# PX4uNode_V0_2_1.net
KiCad netlist of a schematic drawn in EAGLE
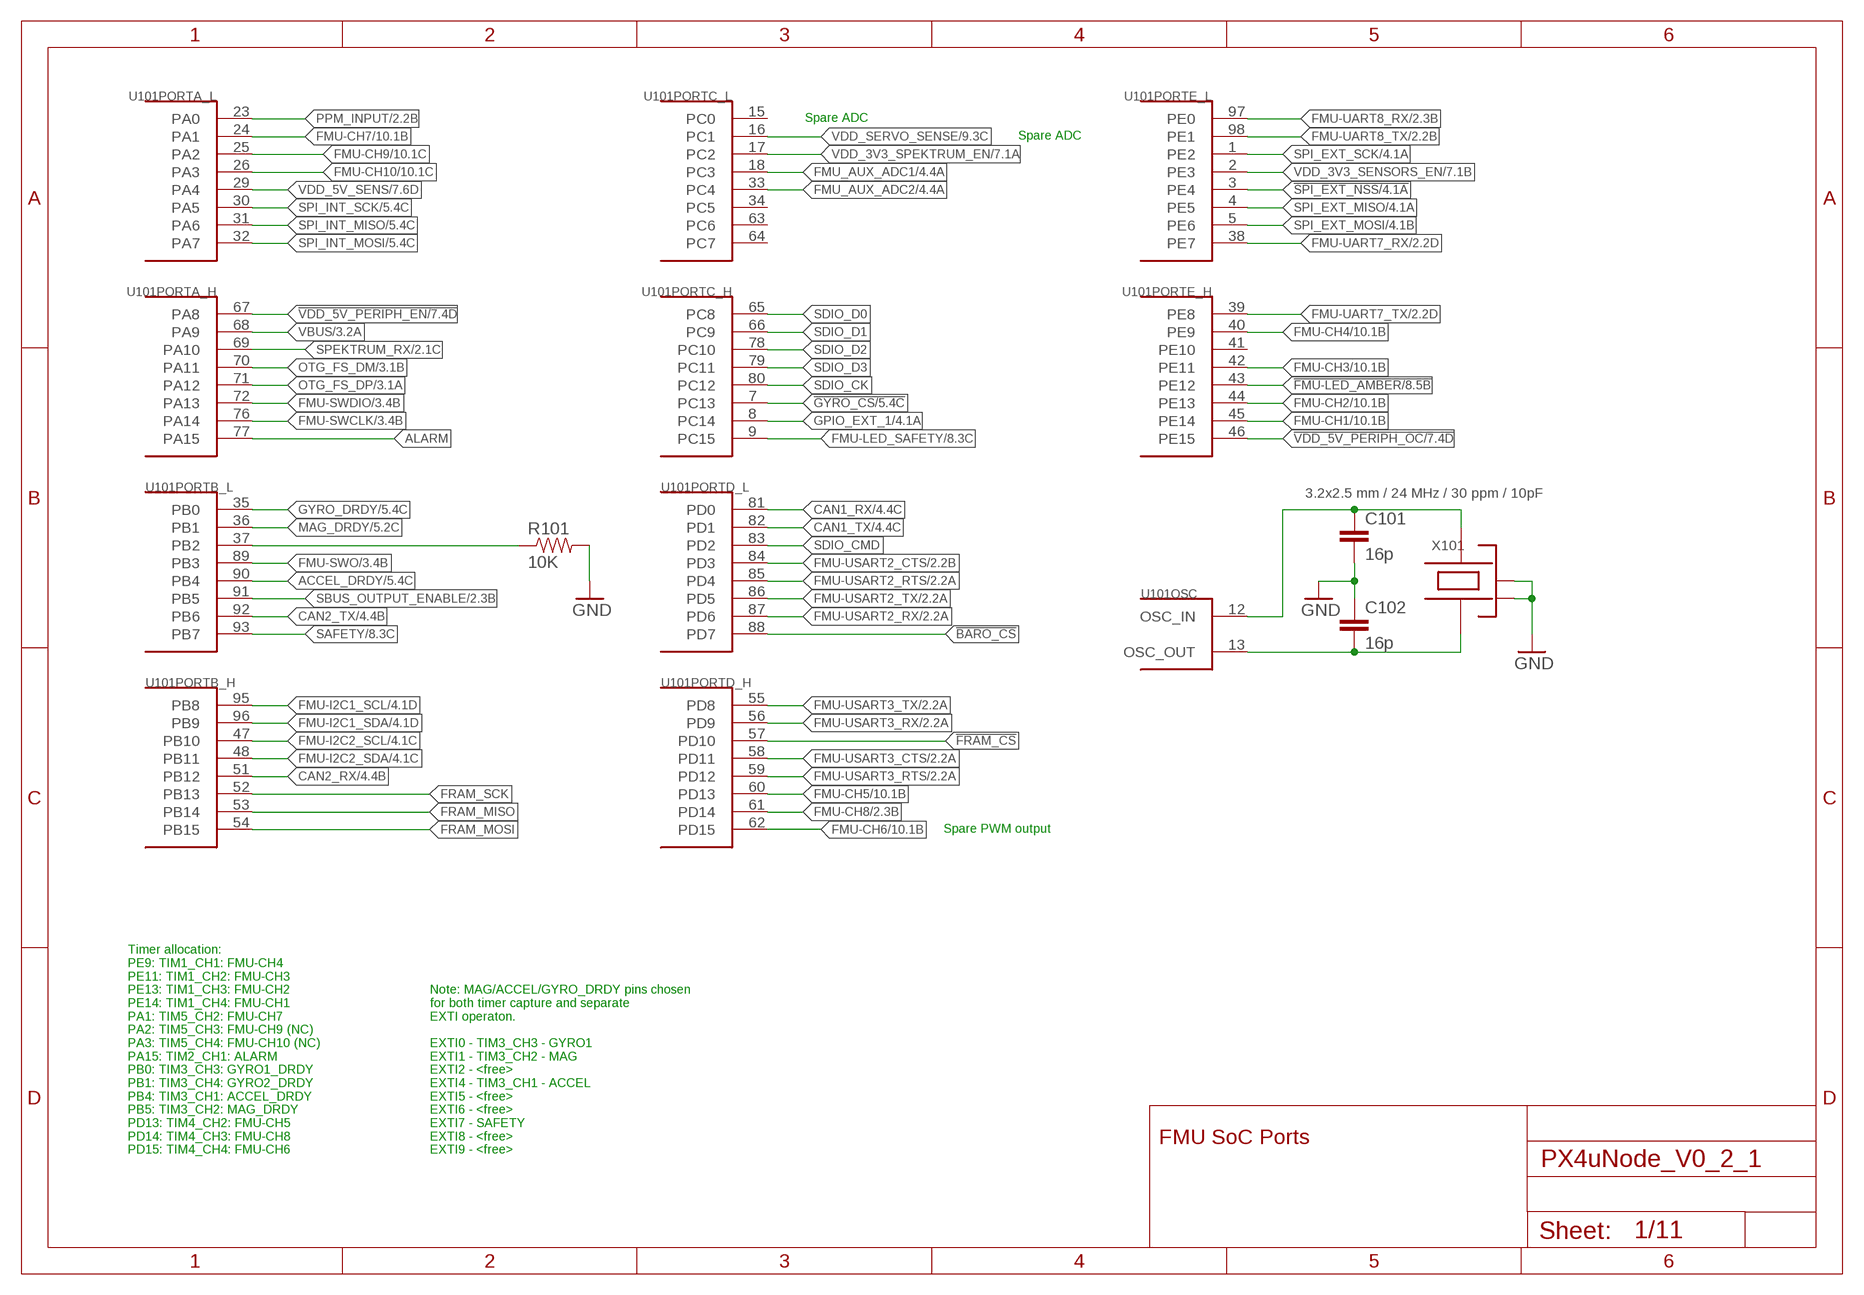
[diagram p0: schematic, sheet 1]
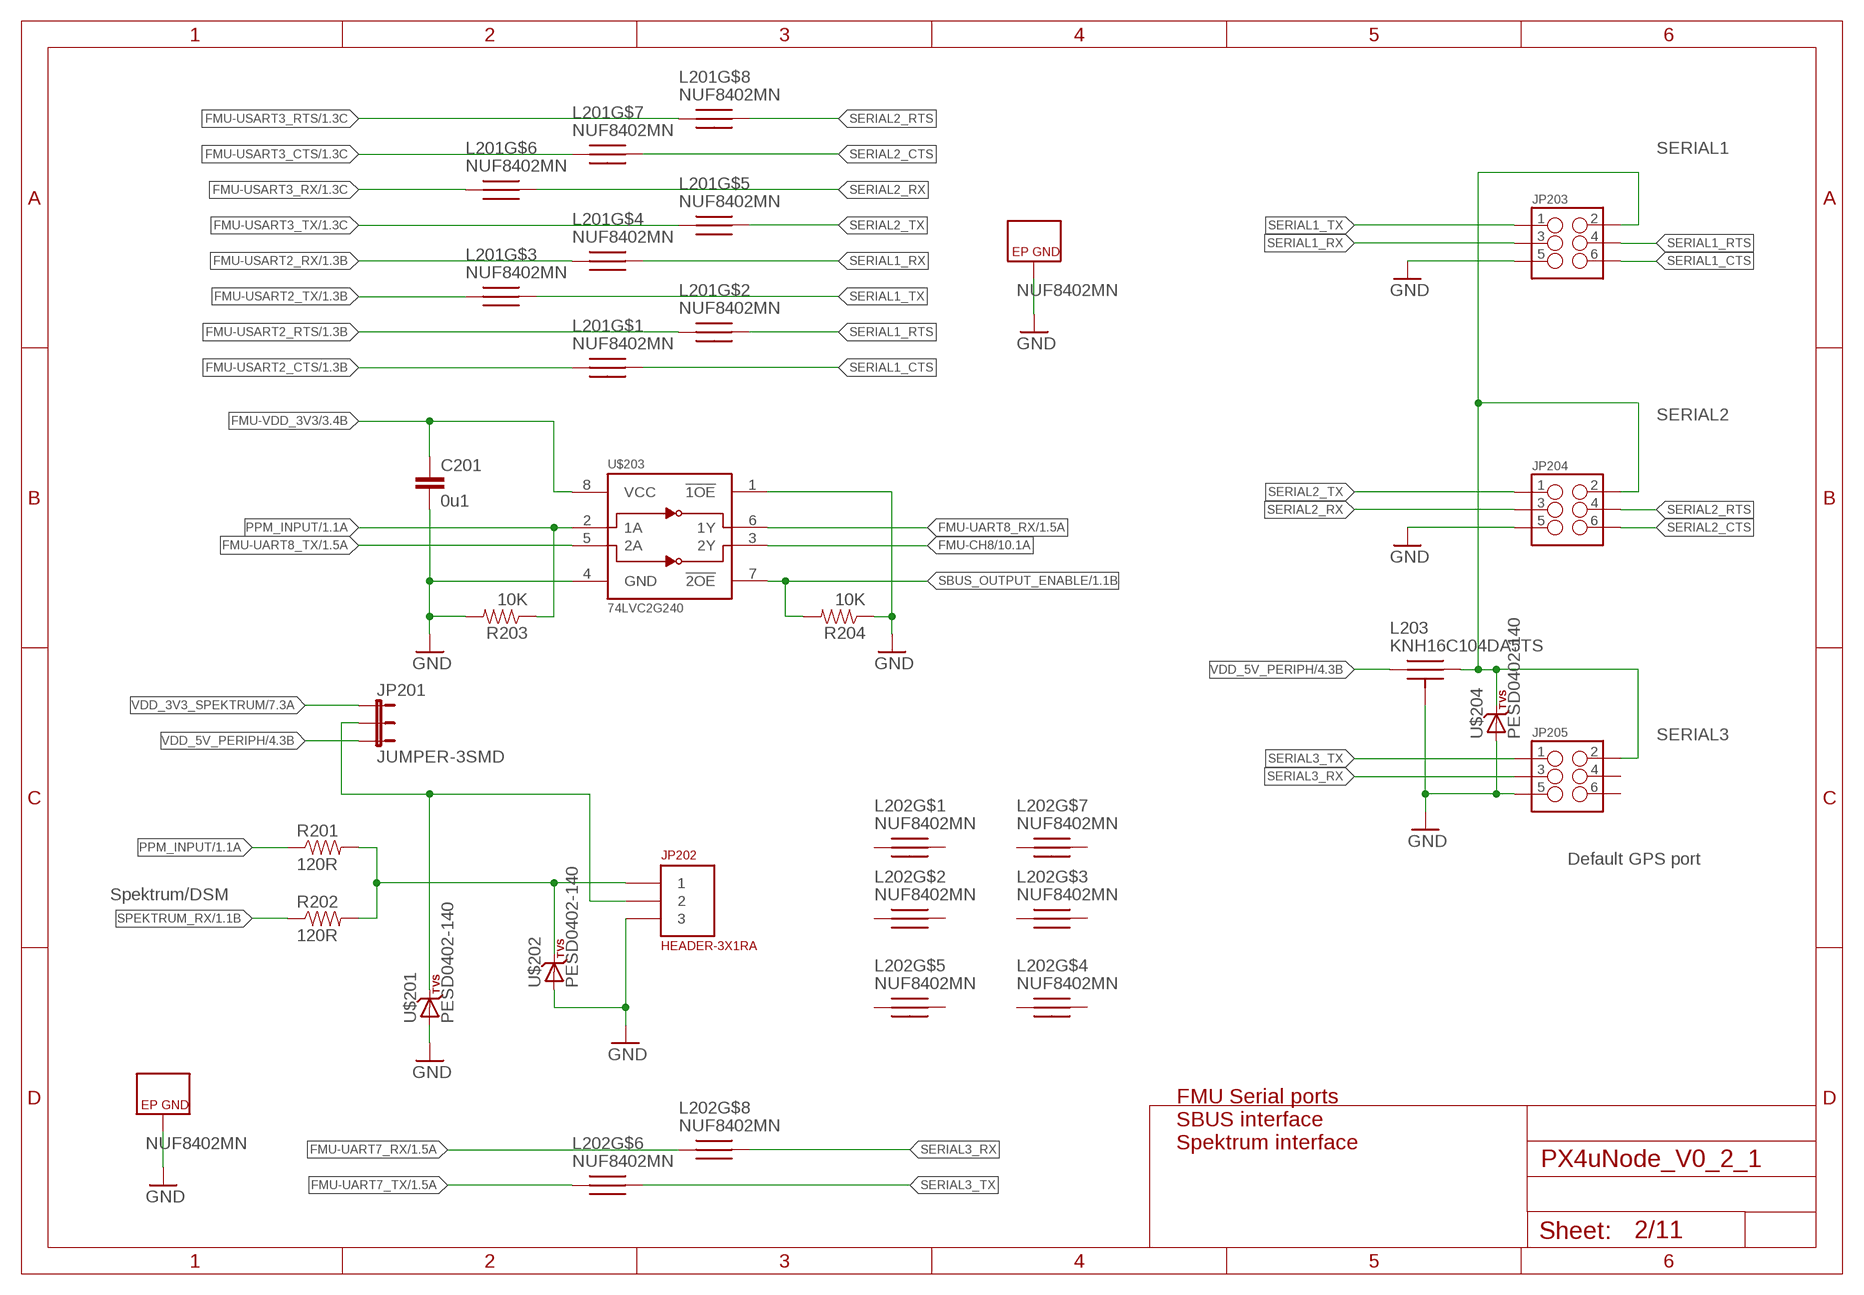
[diagram p1: schematic, sheet 2]
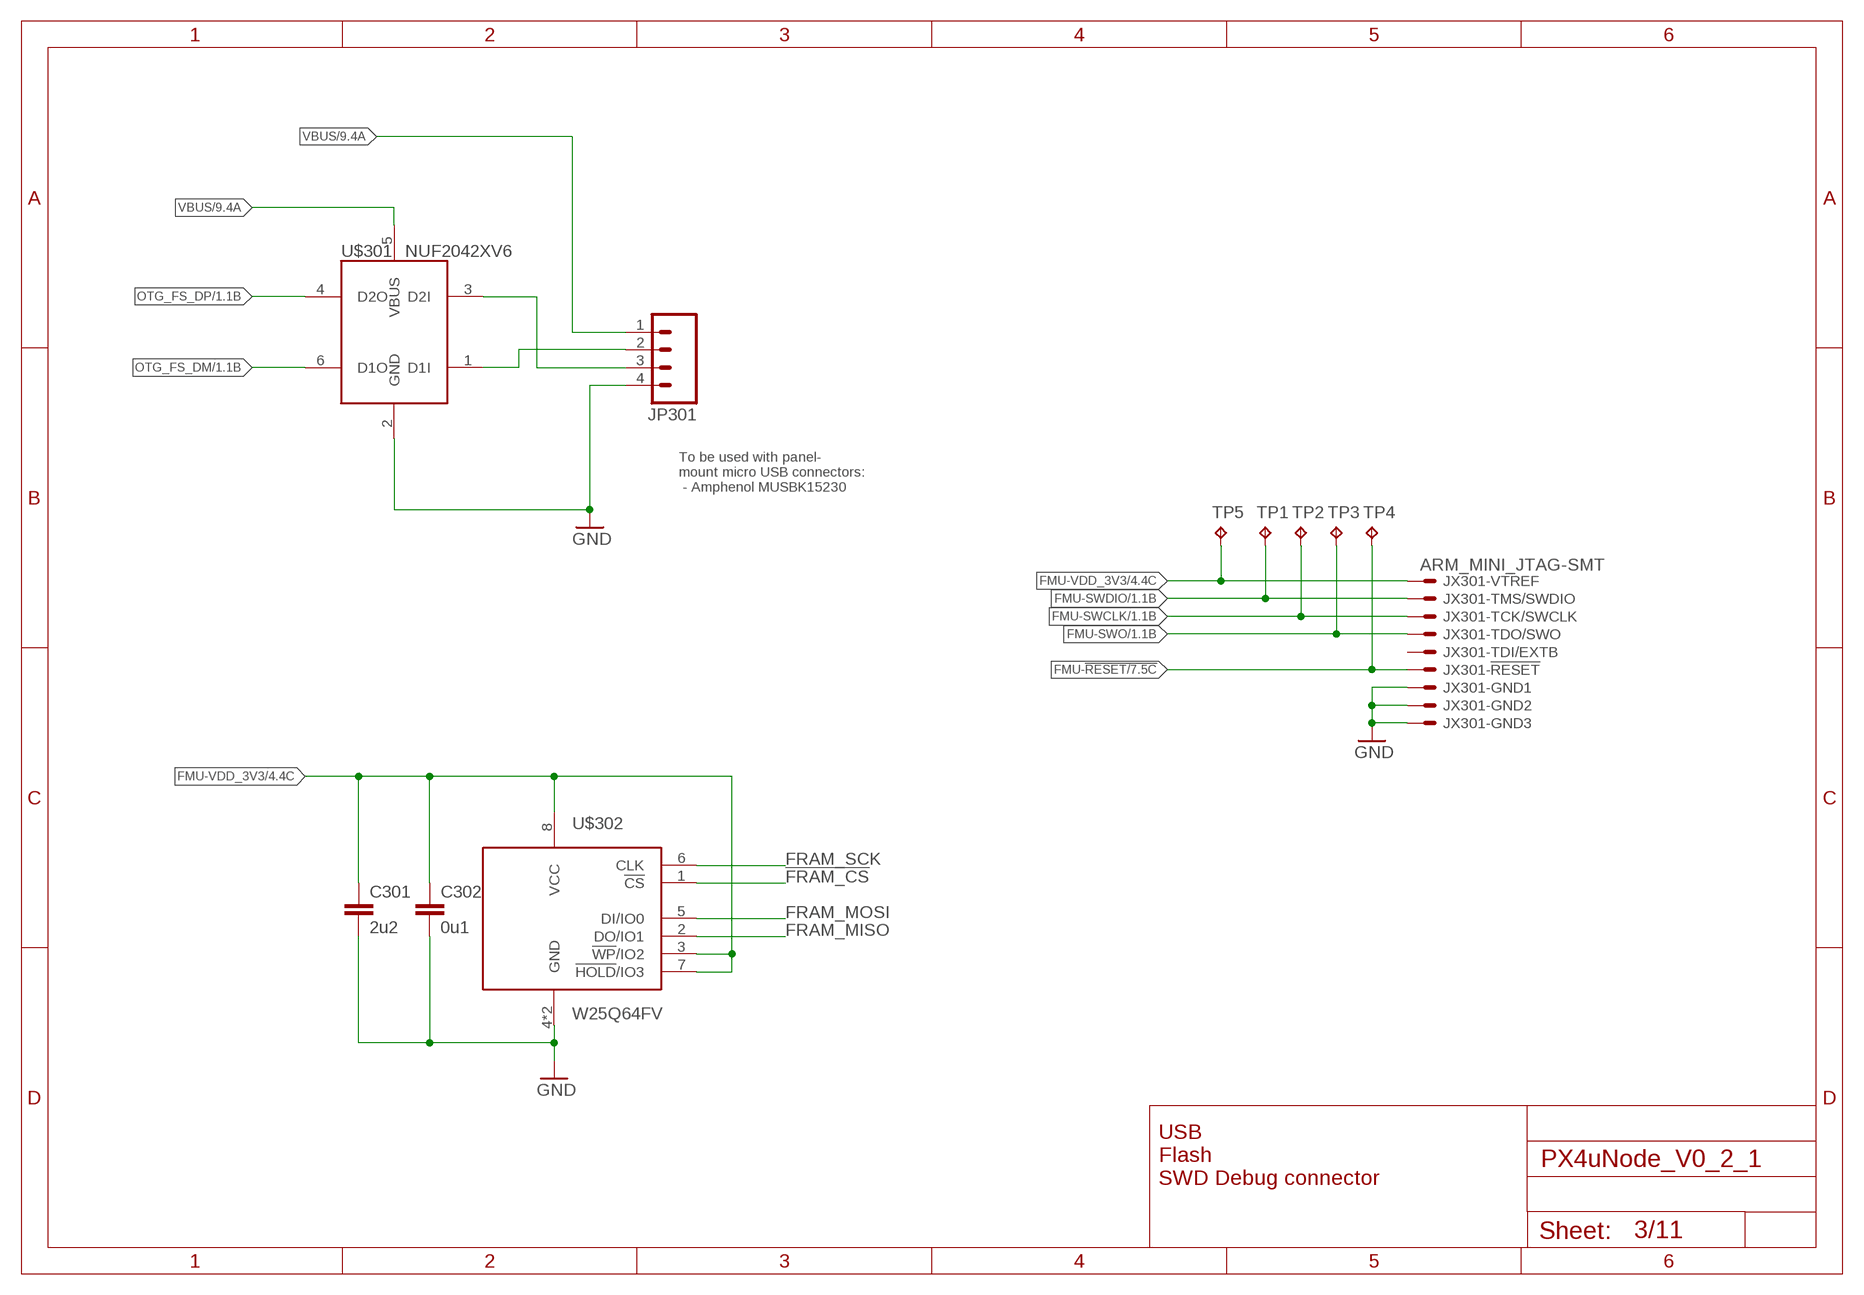
[diagram p2: schematic, sheet 3]
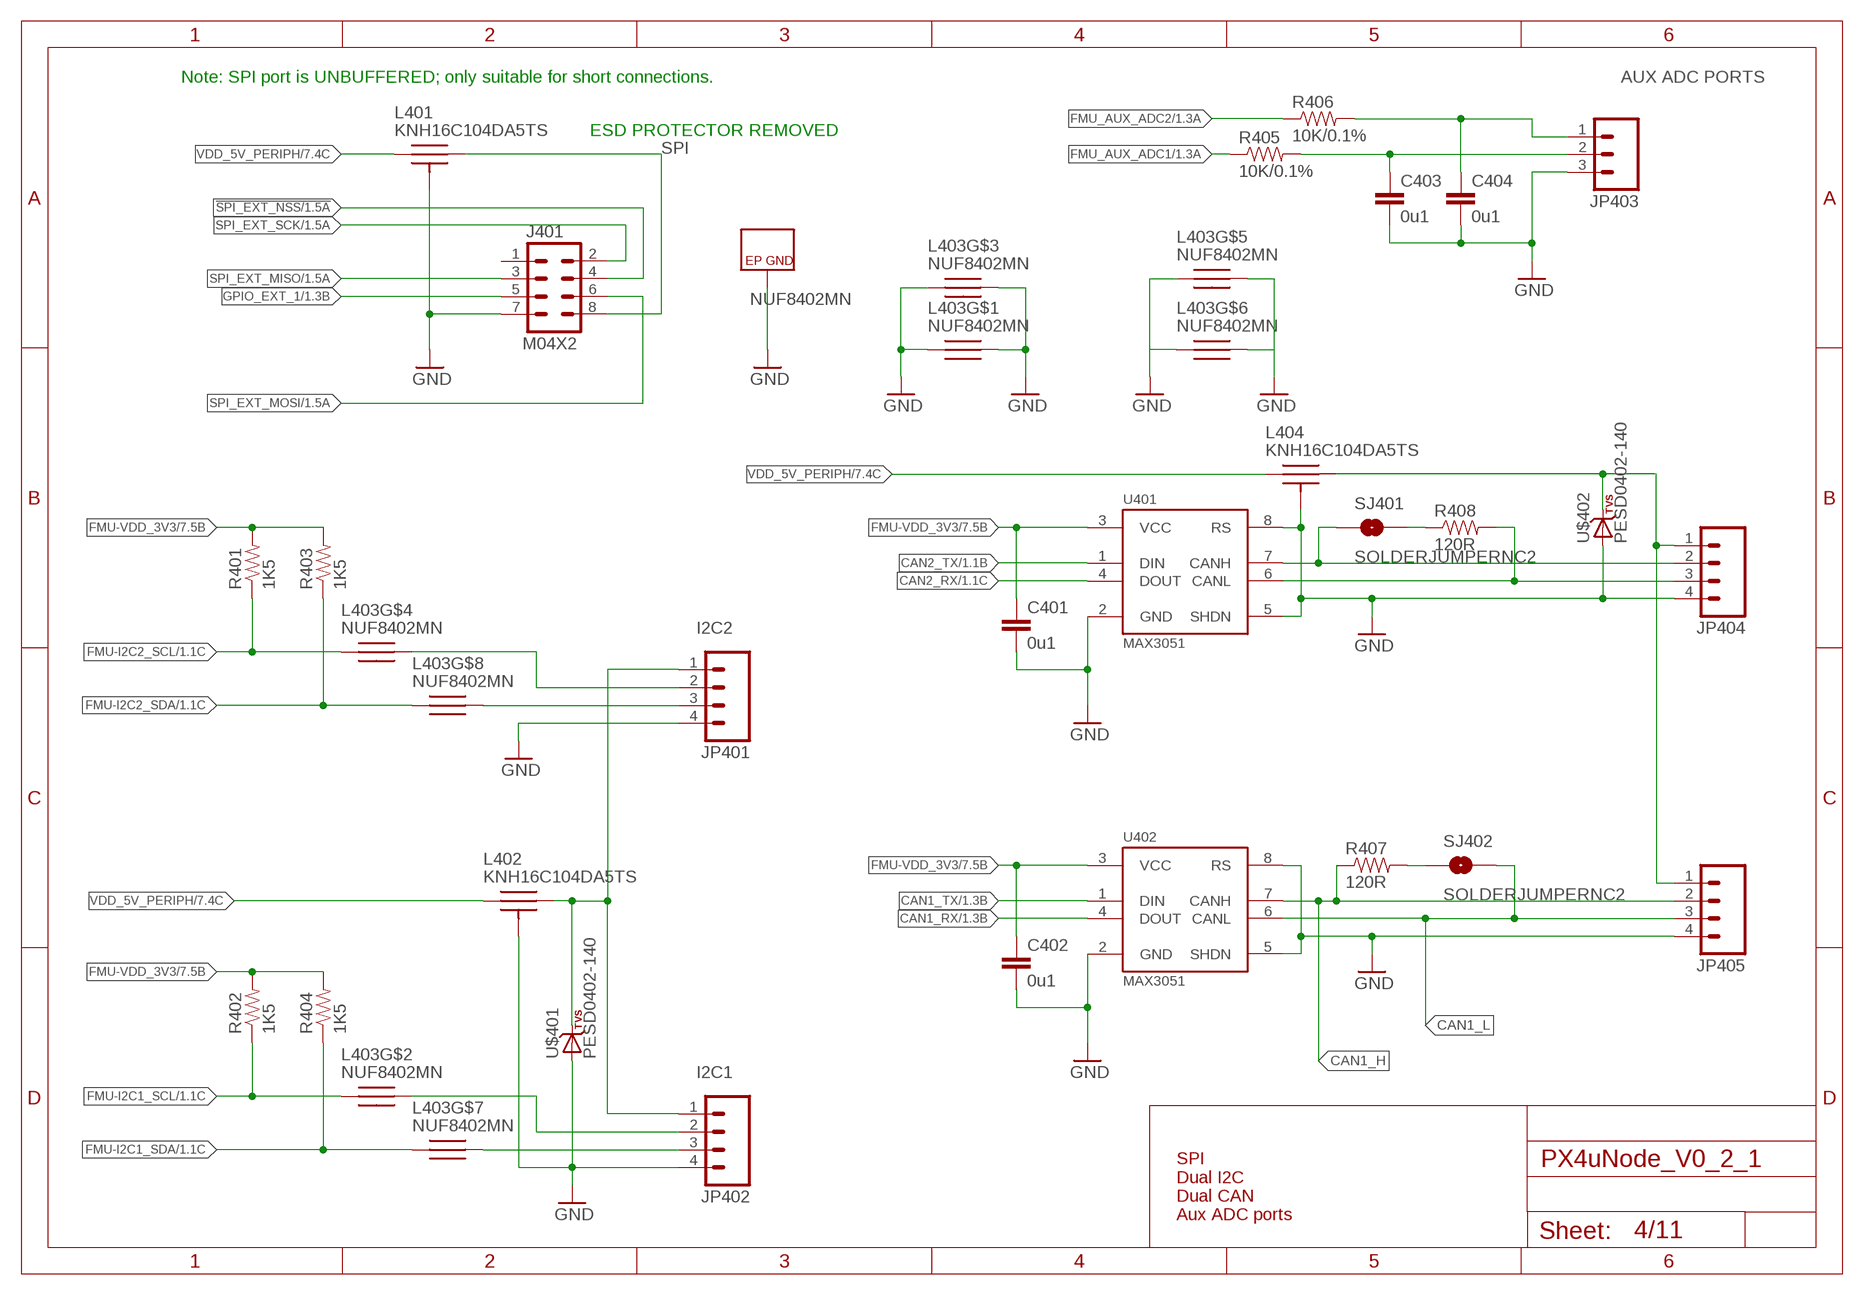
[diagram p3: schematic, sheet 4]
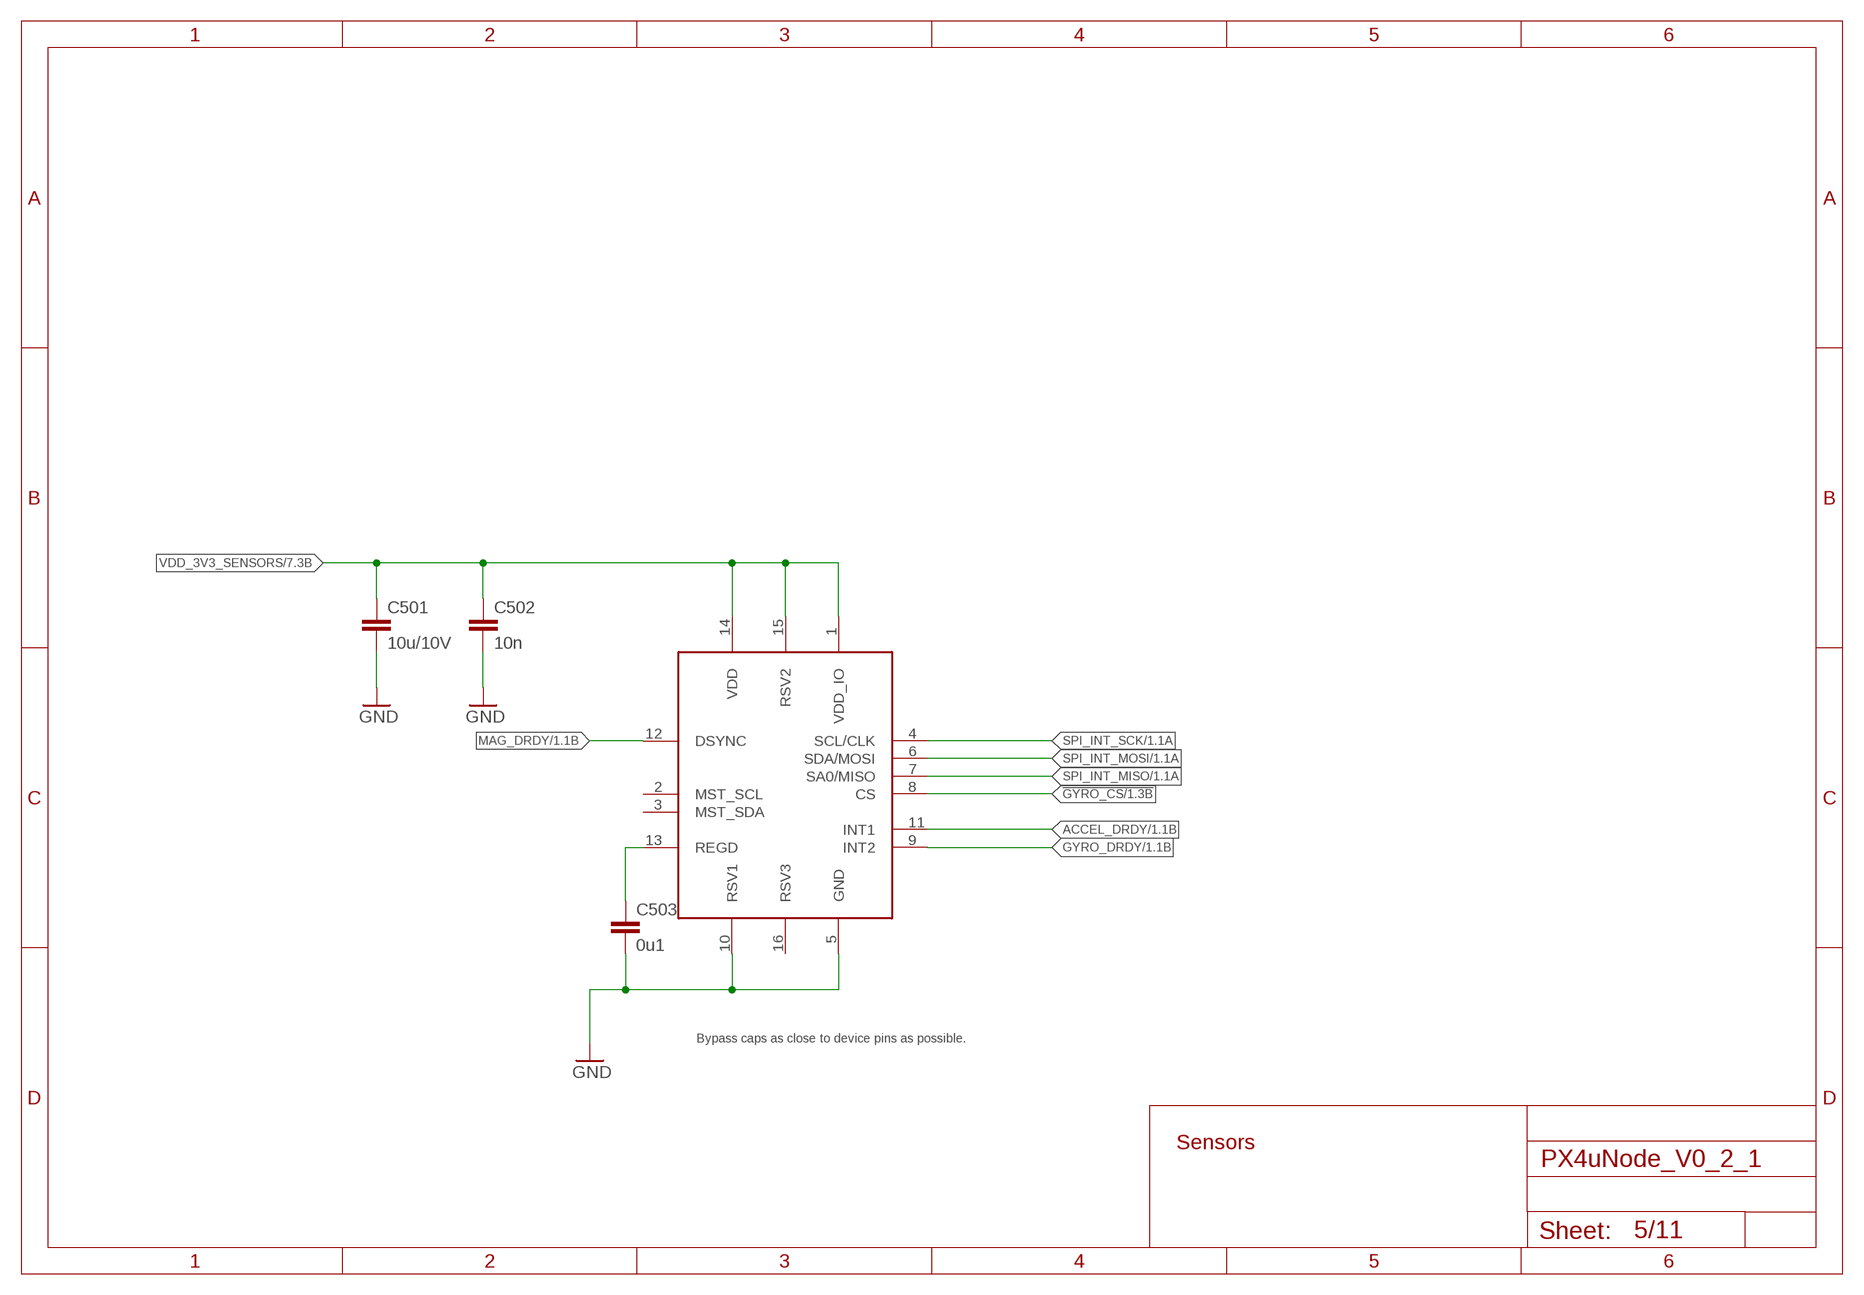
[diagram p4: schematic, sheet 5]
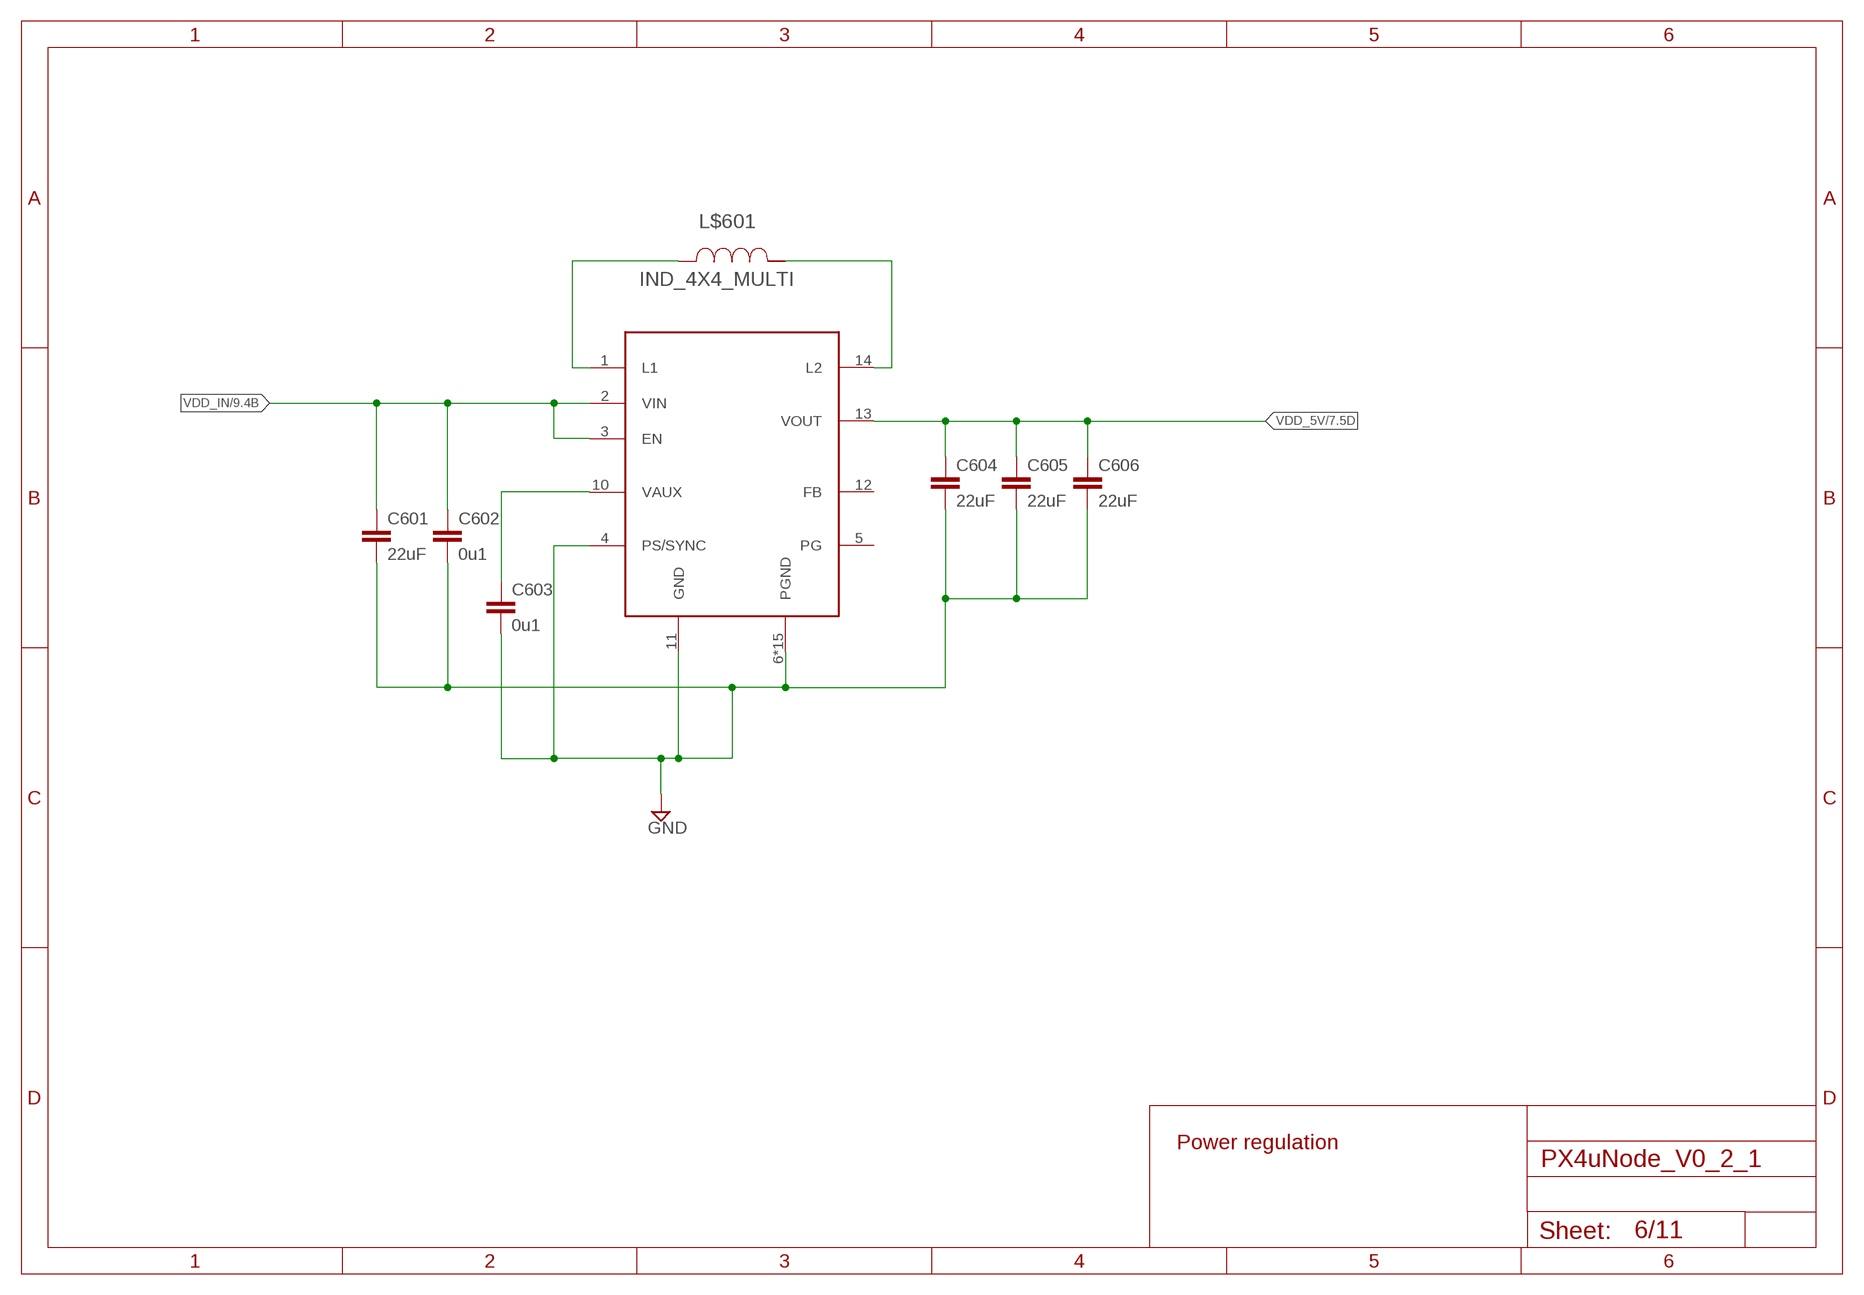
[diagram p5: schematic, sheet 6]
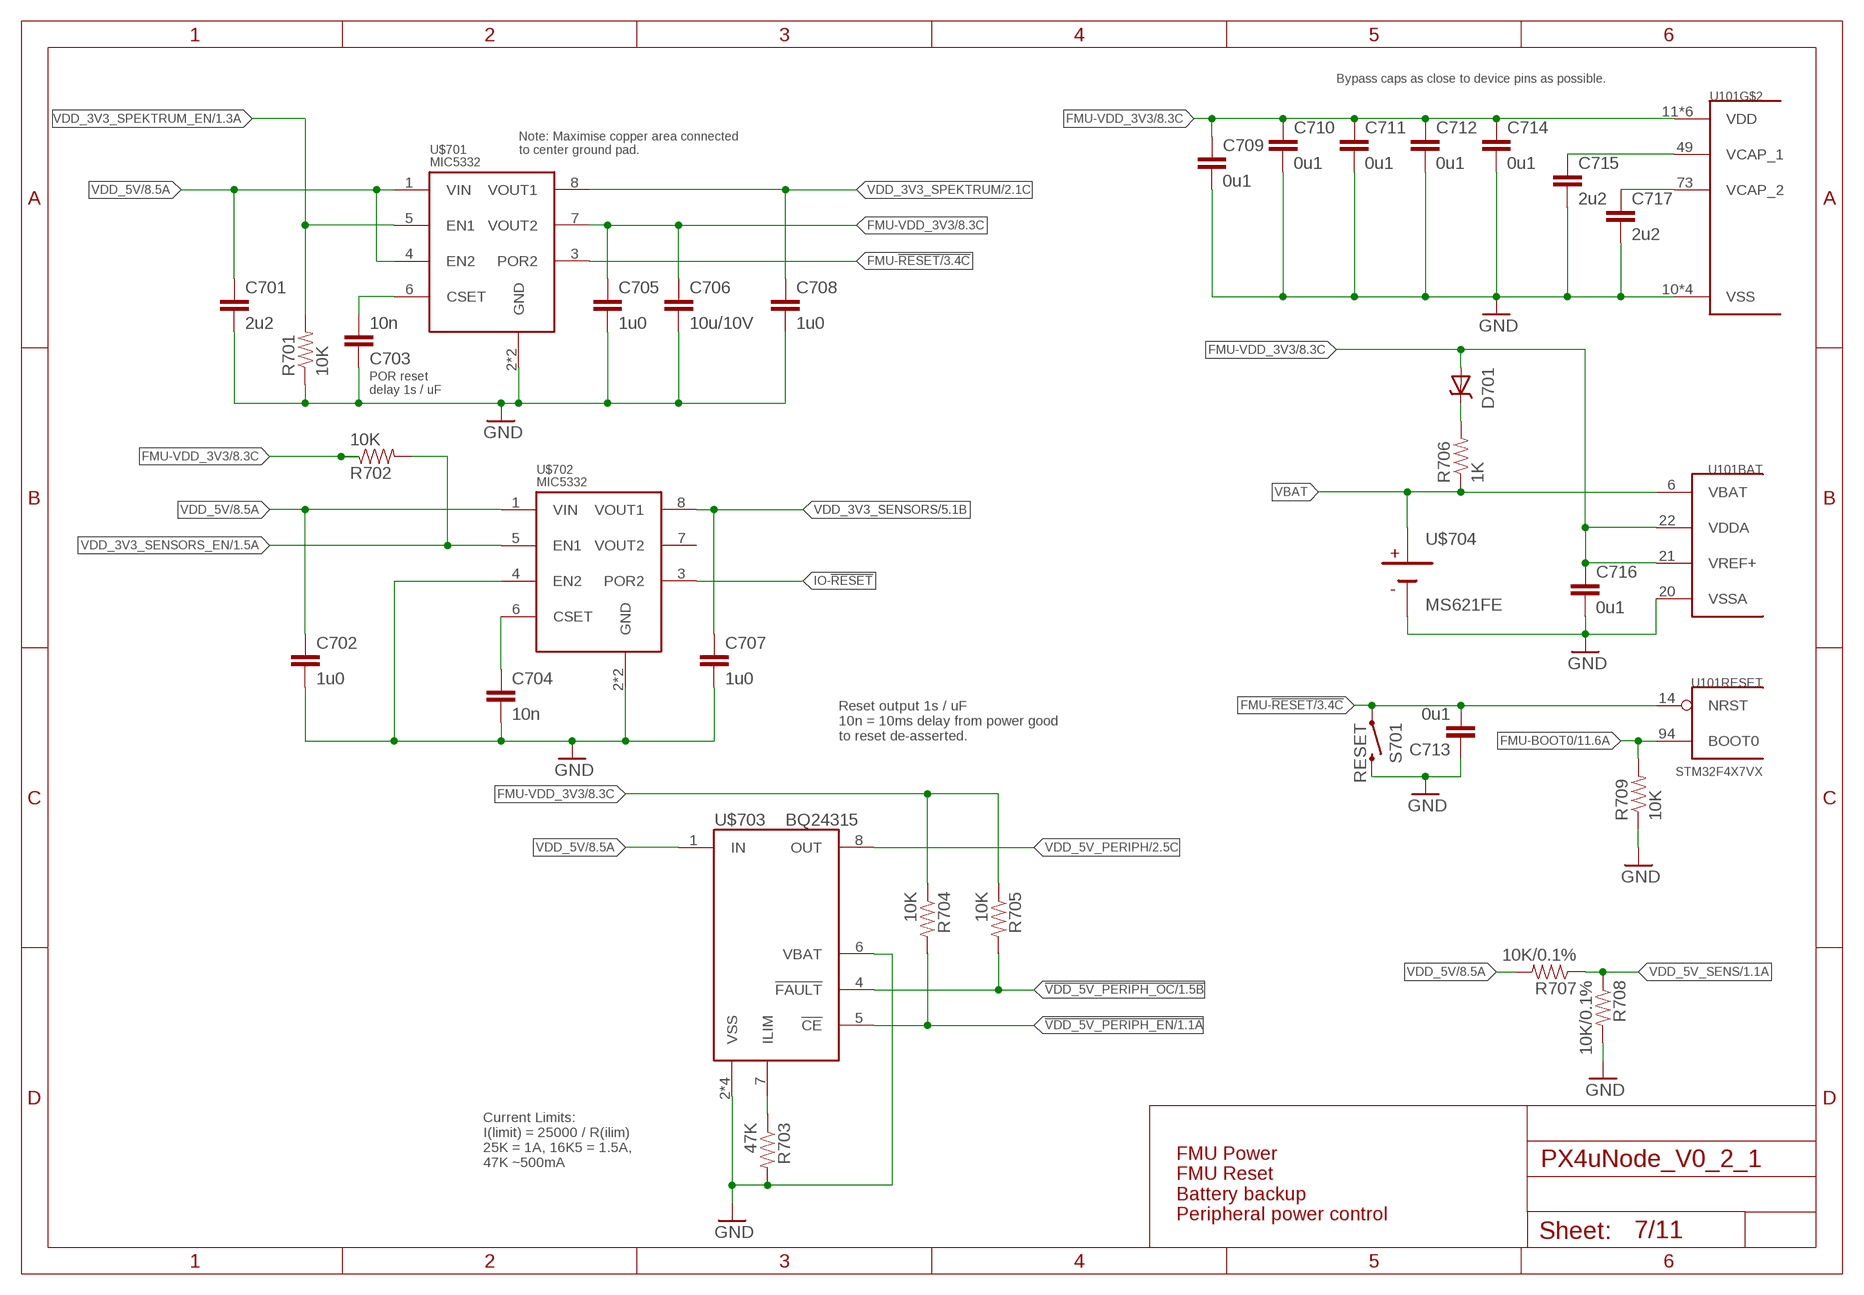
[diagram p6: schematic, sheet 7]
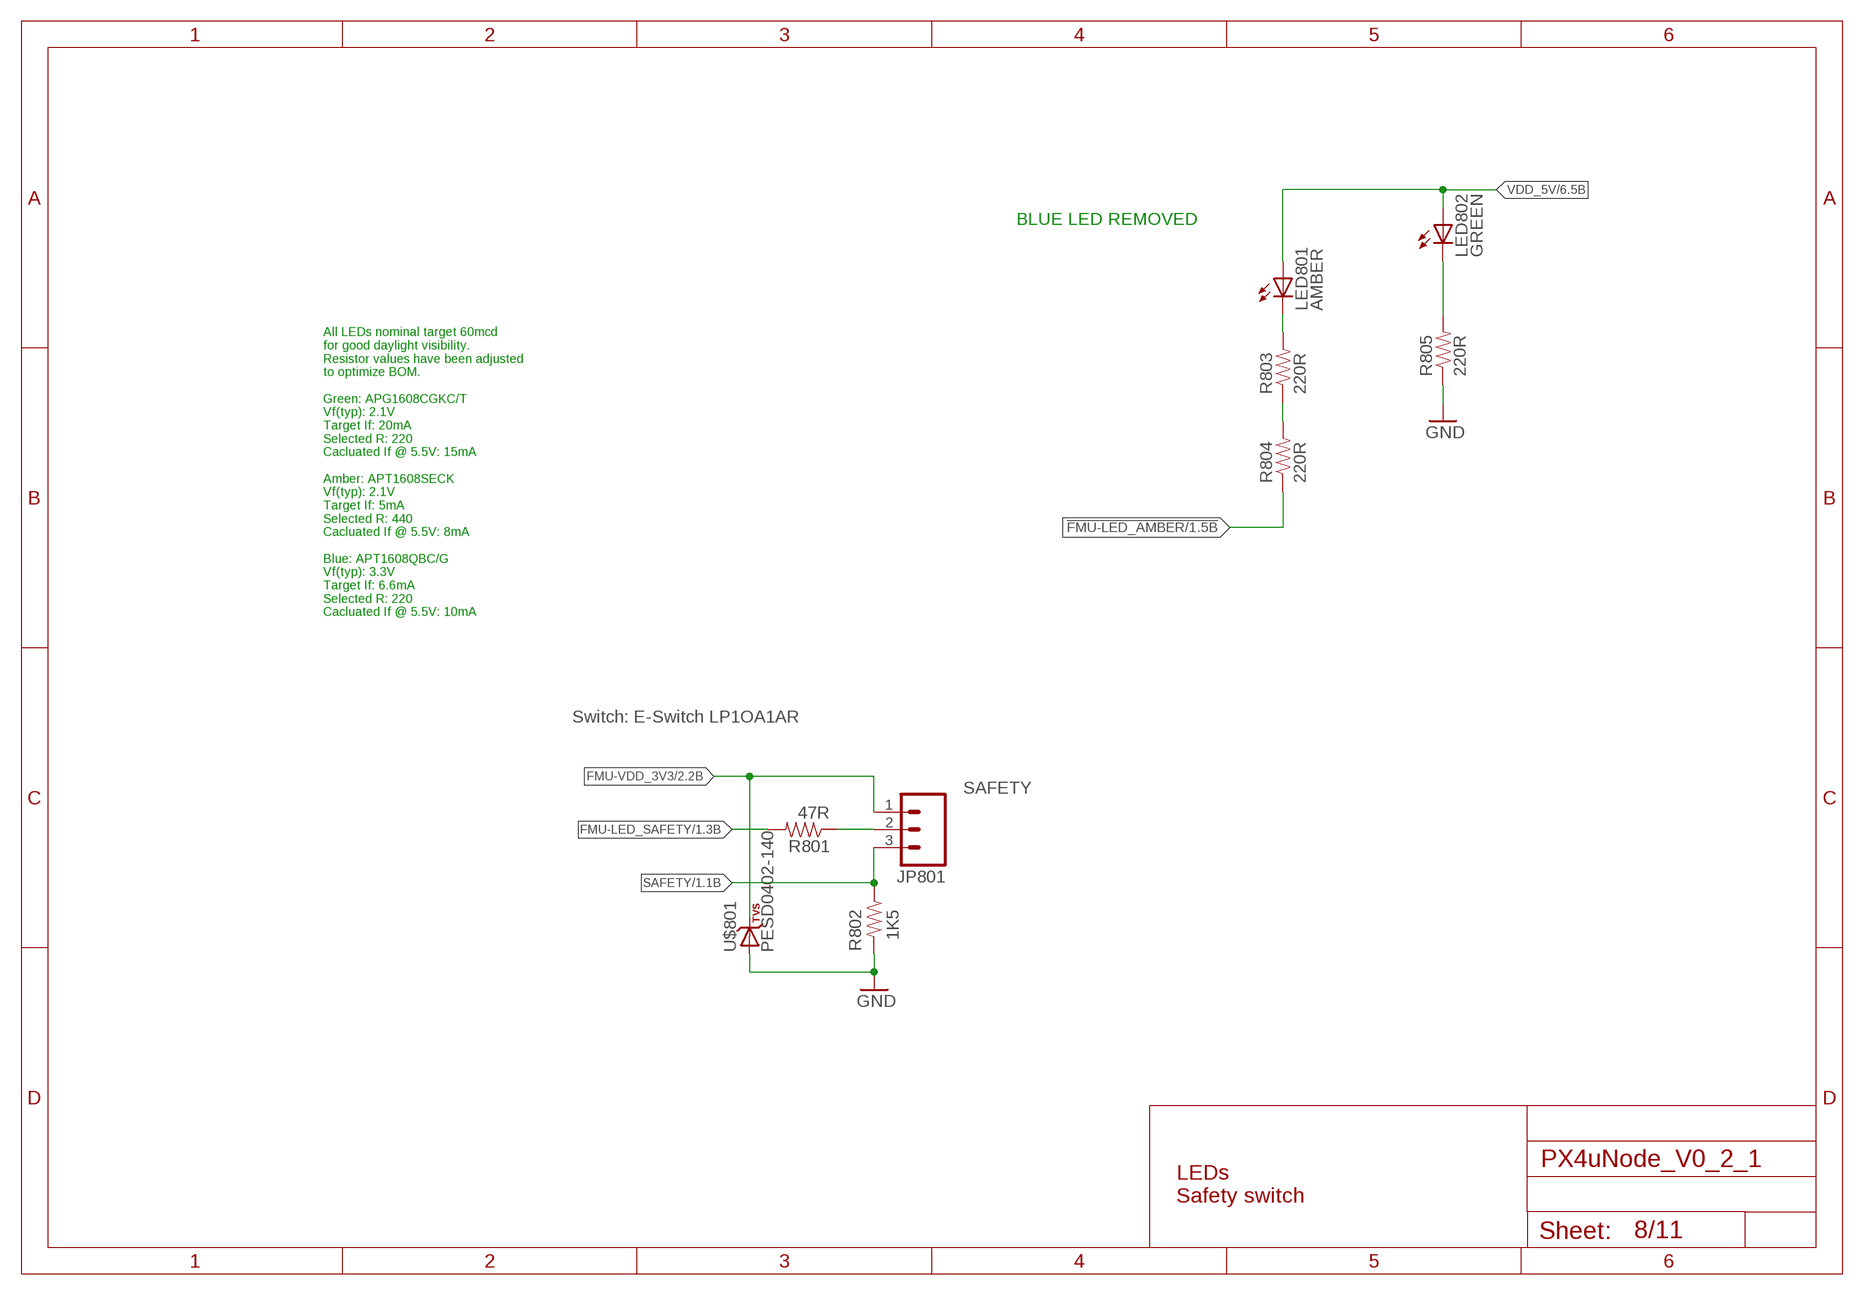
[diagram p7: schematic, sheet 8]
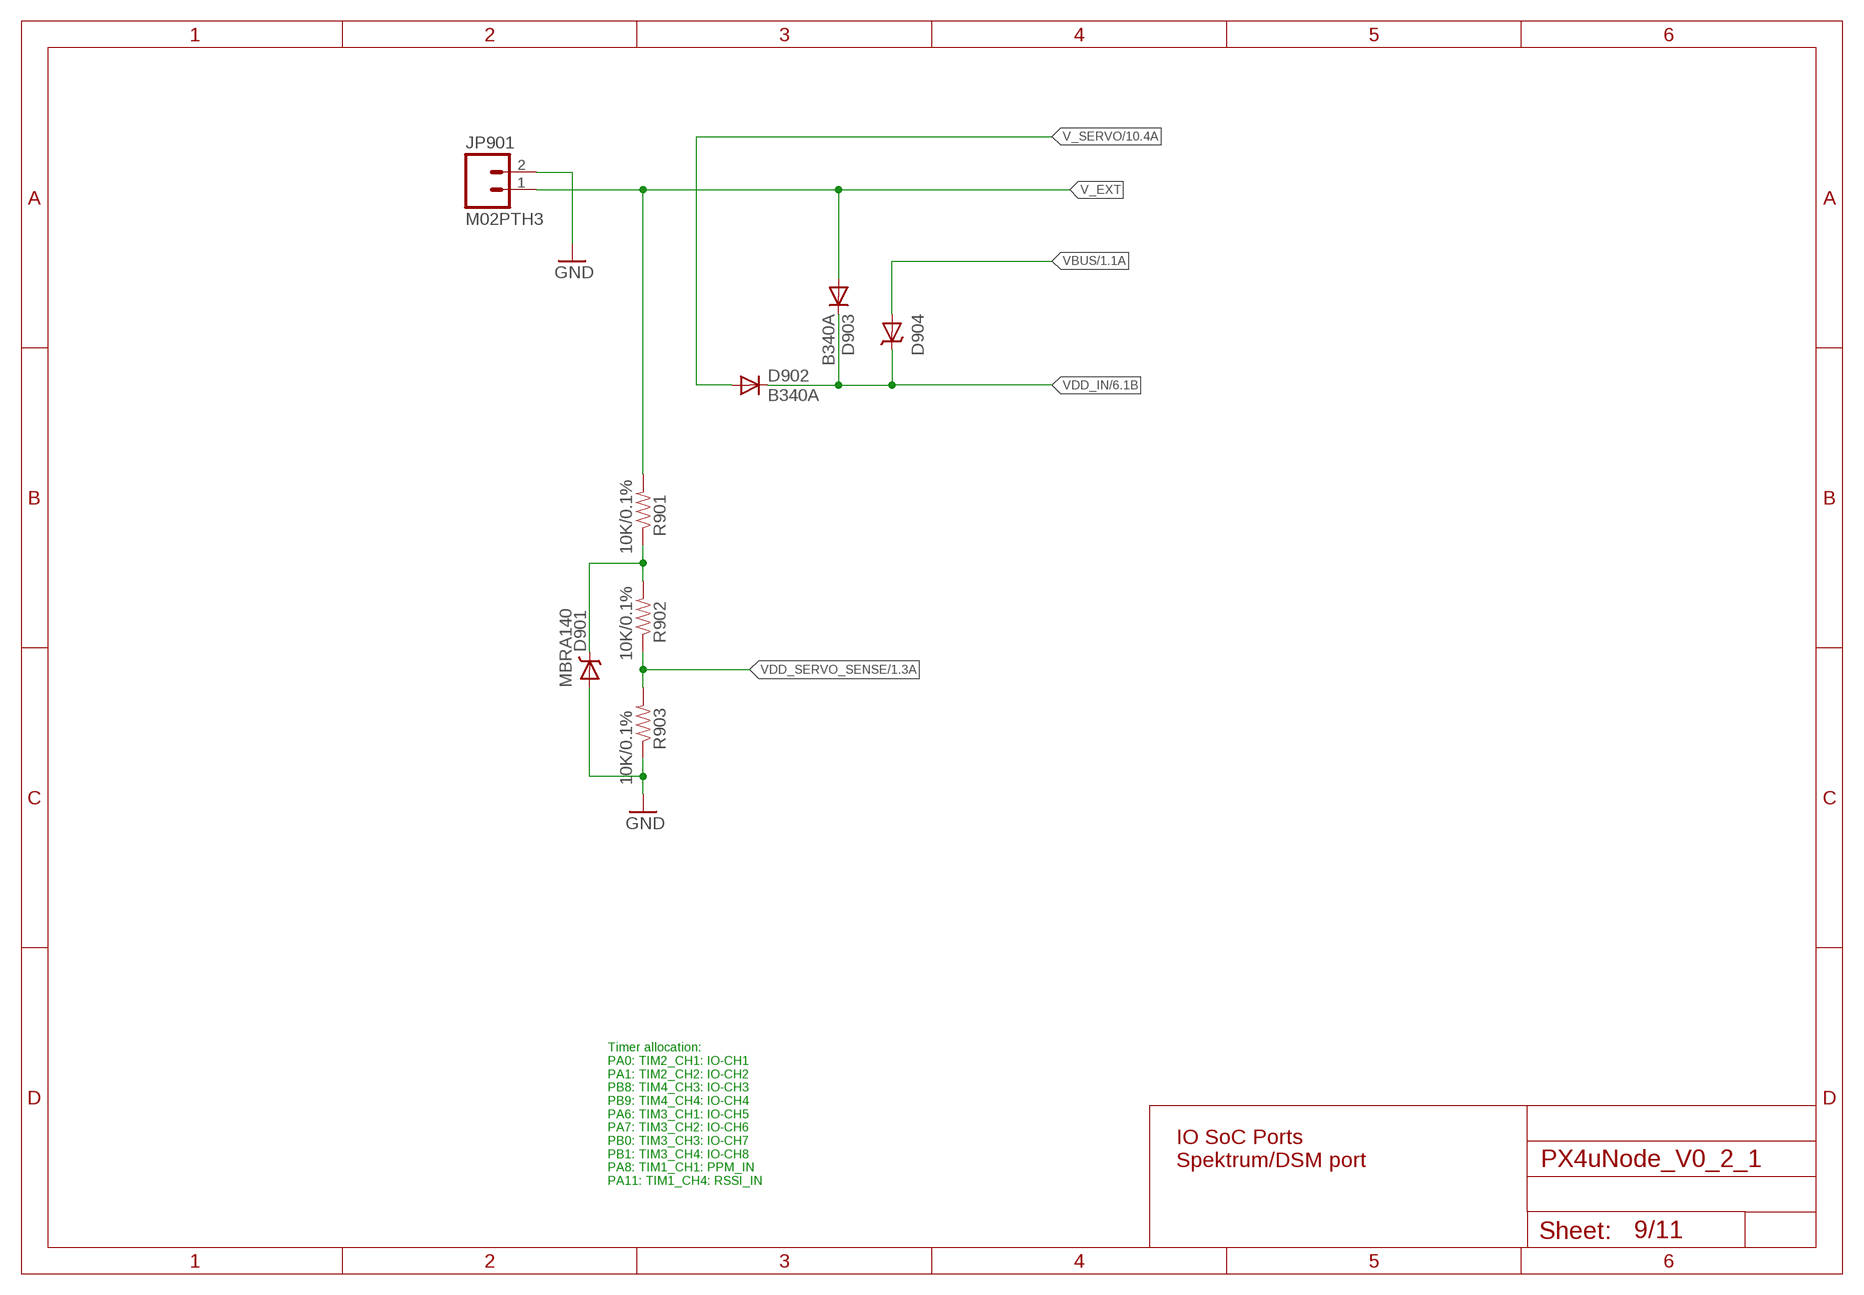
[diagram p8: schematic, sheet 9]
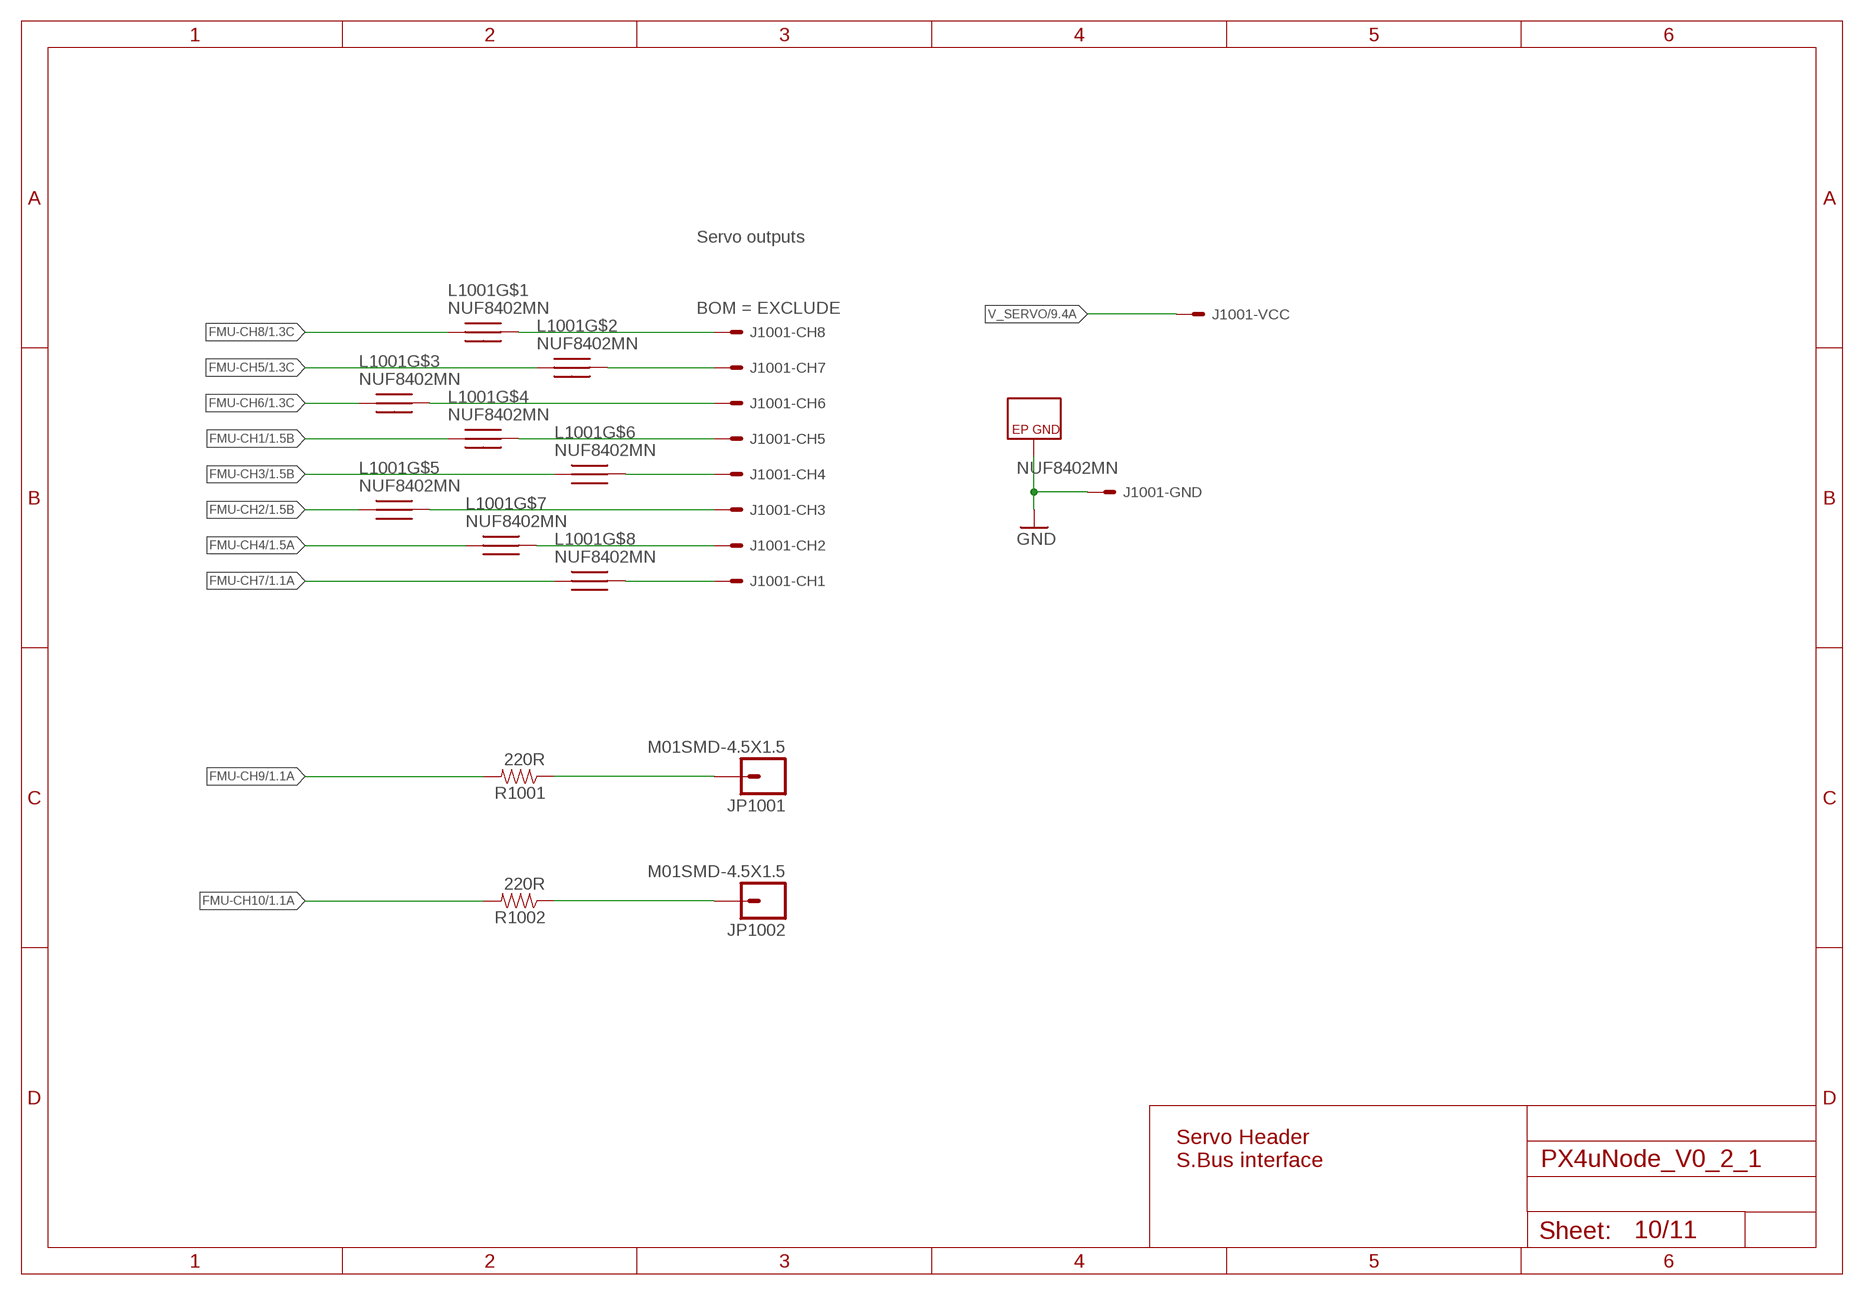
[diagram p9: schematic, sheet 10]
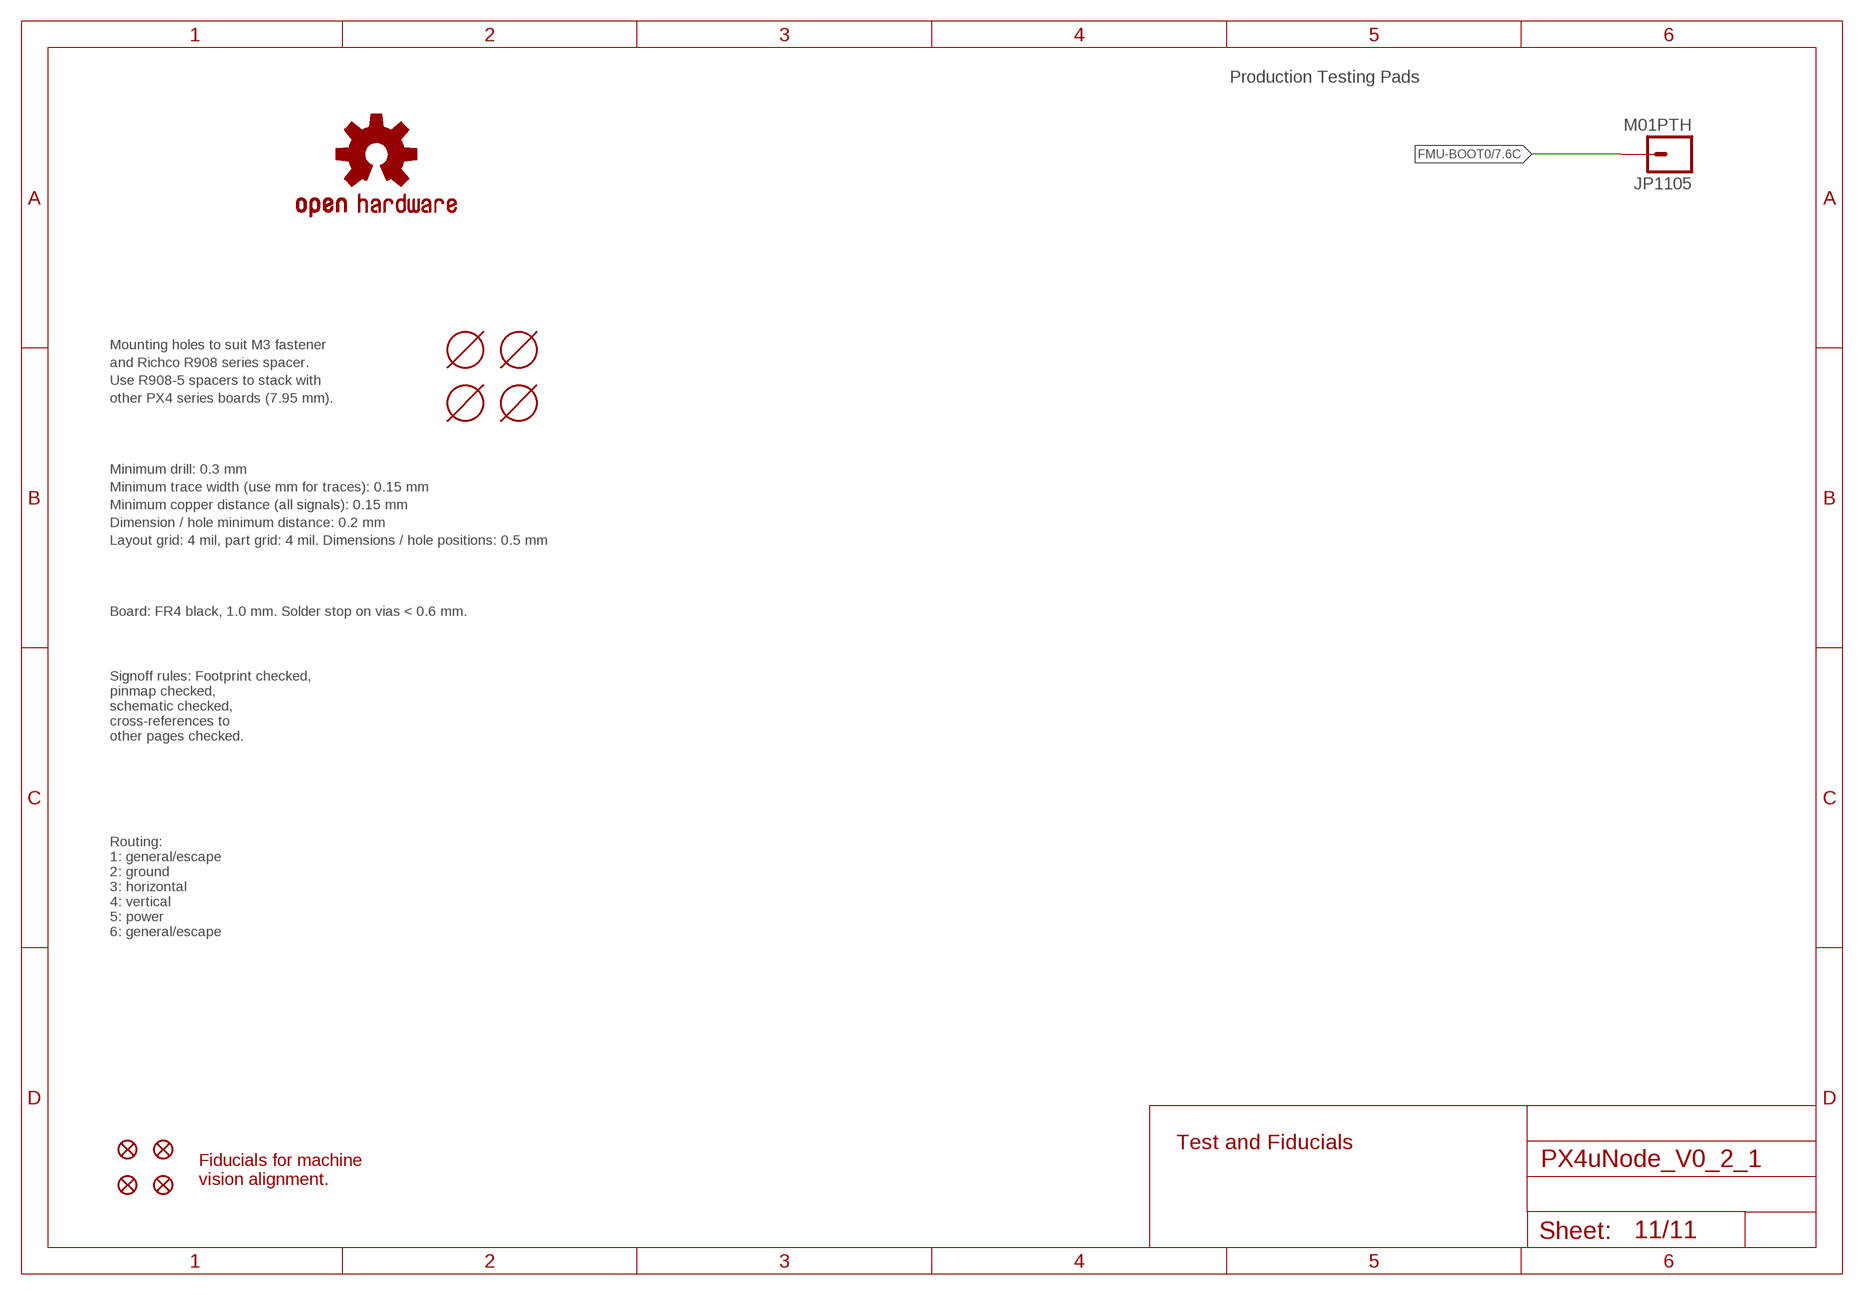
[diagram p10: schematic, sheet 11]

(export (version "E")
  (design (tool "Eeschema 10.0.6"))
  (components
    (comp (ref "JP801")
      (value "M03PTH")
      (footprint "eagle-import:1X03")
      (libsource (lib "eagle-import") (part "M03PTH"))
    )
    (comp (ref "LED801")
      (value "AMBER")
      (footprint "eagle-import:0603-LED")
      (fields (field (name "PARTNO") "APTD1608SECK"))
      (libsource (lib "eagle-import") (part "LED0603"))
    )
    (comp (ref "LED802")
      (value "GREEN")
      (footprint "eagle-import:0603-LED")
      (fields (field (name "PARTNO") "APTD1608CGCK"))
      (libsource (lib "eagle-import") (part "LED0603"))
    )
    (comp (ref "R801")
      (value "47R")
      (footprint "eagle-import:0402-RES")
      (fields (field (name "PARTNO") "RC0402JR-0747RL"))
      (libsource (lib "eagle-import") (part "RESISTOR0402-RES"))
    )
    (comp (ref "R802")
      (value "1K5")
      (footprint "eagle-import:0402-RES")
      (fields (field (name "PARTNO") "RC0402FR-071K5L"))
      (libsource (lib "eagle-import") (part "RESISTOR0402-RES"))
    )
    (comp (ref "R803")
      (value "220R")
      (footprint "eagle-import:0402-RES")
      (fields (field (name "PARTNO") "RC0402FR-07220RL"))
      (libsource (lib "eagle-import") (part "RESISTOR0402-RES"))
    )
    (comp (ref "R804")
      (value "220R")
      (footprint "eagle-import:0402-RES")
      (fields (field (name "PARTNO") "RC0402FR-07220RL"))
      (libsource (lib "eagle-import") (part "RESISTOR0402-RES"))
    )
    (comp (ref "R805")
      (value "220R")
      (footprint "eagle-import:0402-RES")
      (fields (field (name "PARTNO") "RC0402FR-07220RL"))
      (libsource (lib "eagle-import") (part "RESISTOR0402-RES"))
    )
    (comp (ref "U$801")
      (value "PESD0402-140")
      (footprint "eagle-import:0402-TVS")
      (libsource (lib "eagle-import") (part "DIODE-TVS"))
    )
    (comp (ref "D901")
      (value "DIODE-SCHOTTKY")
      (footprint "eagle-import:SOD-523")
      (fields (field (name "PARTNO") "MBRA140"))
      (libsource (lib "eagle-import") (part "DIODE-SCHOTTKY"))
    )
    (comp (ref "D902")
      (value "B340A")
      (footprint "eagle-import:SMA-DIODE")
      (libsource (lib "eagle-import") (part "DIODESMA"))
    )
    (comp (ref "D903")
      (value "B340A")
      (footprint "eagle-import:SMA-DIODE")
      (libsource (lib "eagle-import") (part "DIODESMA"))
    )
    (comp (ref "D904")
      (value "MSS1P4-M3")
      (footprint "eagle-import:MICROSMP")
      (fields (field (name "PARTNO") "MSS1P4-M3/89A"))
      (libsource (lib "eagle-import") (part "DIODE-SCHOTTKY_MSMP"))
    )
    (comp (ref "JP901")
      (value "M02PTH3")
      (footprint "eagle-import:1X02_LONGPADS")
      (libsource (lib "eagle-import") (part "M02PTH3"))
    )
    (comp (ref "R901")
      (value "10K/0.1%")
      (footprint "eagle-import:0402-RES")
      (fields (field (name "PARTNO") "ERA-2AEB103X"))
      (libsource (lib "eagle-import") (part "RESISTOR0402-RES"))
    )
    (comp (ref "R902")
      (value "10K/0.1%")
      (footprint "eagle-import:0402-RES")
      (fields (field (name "PARTNO") "ERA-2AEB103X"))
      (libsource (lib "eagle-import") (part "RESISTOR0402-RES"))
    )
    (comp (ref "R903")
      (value "10K/0.1%")
      (footprint "eagle-import:0402-RES")
      (fields (field (name "PARTNO") "ERA-2AEB103X"))
      (libsource (lib "eagle-import") (part "RESISTOR0402-RES"))
    )
    (comp (ref "C301")
      (value "2u2")
      (footprint "eagle-import:0603-CAP")
      (fields (field (name "PARTNO") "C1608Y5V1C225Z"))
      (libsource (lib "eagle-import") (part "CAP0603"))
    )
    (comp (ref "C302")
      (value "0u1")
      (footprint "eagle-import:0402-CAP")
      (fields (field (name "PARTNO") "CC0402ZRY5V7BB104"))
      (libsource (lib "eagle-import") (part "CAP0402"))
    )
    (comp (ref "JP301")
      (value "M04PTH")
      (footprint "eagle-import:1X04")
      (libsource (lib "eagle-import") (part "M04PTH"))
    )
    (comp (ref "JX301")
      (value "ARM_MINI_JTAG-SMT")
      (footprint "eagle-import:FTSH-105-01-XXX-DV-K")
      (fields (field (name "BOM") "EXCLUDE") (field (name "PARTNO") "M50-3900542"))
      (libsource (lib "eagle-import") (part "ARM_MINI_JTAG-SMT"))
    )
    (comp (ref "TP1")
      (value "TPTP20R")
      (footprint "eagle-import:TP20R")
      (libsource (lib "eagle-import") (part "TPTP20R"))
    )
    (comp (ref "TP2")
      (value "TPTP20R")
      (footprint "eagle-import:TP20R")
      (libsource (lib "eagle-import") (part "TPTP20R"))
    )
    (comp (ref "TP3")
      (value "TPTP20R")
      (footprint "eagle-import:TP20R")
      (libsource (lib "eagle-import") (part "TPTP20R"))
    )
    (comp (ref "TP4")
      (value "TPTP20R")
      (footprint "eagle-import:TP20R")
      (libsource (lib "eagle-import") (part "TPTP20R"))
    )
    (comp (ref "TP5")
      (value "TPTP20R")
      (footprint "eagle-import:TP20R")
      (libsource (lib "eagle-import") (part "TPTP20R"))
    )
    (comp (ref "U$301")
      (value "NUF2042XV6")
      (footprint "eagle-import:SOT563-6")
      (libsource (lib "eagle-import") (part "NUF2042XV6"))
    )
    (comp (ref "U$302")
      (value "W25Q64FV")
      (footprint "eagle-import:WSON-8-5X6")
      (fields (field (name "PARTNO") "W25Q64FVZP"))
      (libsource (lib "eagle-import") (part "W25Q64FV"))
    )
    (comp (ref "C401")
      (value "0u1")
      (footprint "eagle-import:0402-CAP")
      (fields (field (name "PARTNO") "CC0402ZRY5V7BB104"))
      (libsource (lib "eagle-import") (part "CAP0402"))
    )
    (comp (ref "C402")
      (value "0u1")
      (footprint "eagle-import:0402-CAP")
      (fields (field (name "PARTNO") "CC0402ZRY5V7BB104"))
      (libsource (lib "eagle-import") (part "CAP0402"))
    )
    (comp (ref "C403")
      (value "0u1")
      (footprint "eagle-import:0402-CAP")
      (fields (field (name "PARTNO") "CC0402ZRY5V7BB104"))
      (libsource (lib "eagle-import") (part "CAP0402"))
    )
    (comp (ref "C404")
      (value "0u1")
      (footprint "eagle-import:0402-CAP")
      (fields (field (name "PARTNO") "CC0402ZRY5V7BB104"))
      (libsource (lib "eagle-import") (part "CAP0402"))
    )
    (comp (ref "J401")
      (value "M04X2")
      (footprint "eagle-import:2X4")
      (libsource (lib "eagle-import") (part "M04X2"))
    )
    (comp (ref "JP401")
      (value "M04PTH")
      (footprint "eagle-import:1X04")
      (libsource (lib "eagle-import") (part "M04PTH"))
    )
    (comp (ref "JP402")
      (value "M04PTH")
      (footprint "eagle-import:1X04")
      (libsource (lib "eagle-import") (part "M04PTH"))
    )
    (comp (ref "JP403")
      (value "M03PTH")
      (footprint "eagle-import:1X03")
      (fields (field (name "PARTNO") "EXCLUDE"))
      (libsource (lib "eagle-import") (part "M03PTH"))
    )
    (comp (ref "JP404")
      (value "M04PTH")
      (footprint "eagle-import:1X04")
      (libsource (lib "eagle-import") (part "M04PTH"))
    )
    (comp (ref "JP405")
      (value "M04PTH")
      (footprint "eagle-import:1X04")
      (libsource (lib "eagle-import") (part "M04PTH"))
    )
    (comp (ref "L401")
      (value "KNH16C104DA5TS")
      (footprint "eagle-import:KYOCERA-KNH16-DA")
      (libsource (lib "eagle-import") (part "KNH16C104DA5TS"))
    )
    (comp (ref "L402")
      (value "KNH16C104DA5TS")
      (footprint "eagle-import:KYOCERA-KNH16-DA")
      (libsource (lib "eagle-import") (part "KNH16C104DA5TS"))
    )
    (comp (ref "L403")
      (value "NUF8402MN")
      (footprint "eagle-import:DFN16-THIN")
      (fields (field (name "PARTNO") "NUF8402MN"))
      (libsource (lib "eagle-import") (part "NUF8402MN"))
    )
    (comp (ref "L404")
      (value "KNH16C104DA5TS")
      (footprint "eagle-import:KYOCERA-KNH16-DA")
      (libsource (lib "eagle-import") (part "KNH16C104DA5TS"))
    )
    (comp (ref "R401")
      (value "1K5")
      (footprint "eagle-import:0402-RES")
      (fields (field (name "PARTNO") "RC0402FR-071K5L"))
      (libsource (lib "eagle-import") (part "RESISTOR0402-RES"))
    )
    (comp (ref "R402")
      (value "1K5")
      (footprint "eagle-import:0402-RES")
      (fields (field (name "PARTNO") "RC0402FR-071K5L"))
      (libsource (lib "eagle-import") (part "RESISTOR0402-RES"))
    )
    (comp (ref "R403")
      (value "1K5")
      (footprint "eagle-import:0402-RES")
      (fields (field (name "PARTNO") "RC0402FR-071K5L"))
      (libsource (lib "eagle-import") (part "RESISTOR0402-RES"))
    )
    (comp (ref "R404")
      (value "1K5")
      (footprint "eagle-import:0402-RES")
      (fields (field (name "PARTNO") "RC0402FR-071K5L"))
      (libsource (lib "eagle-import") (part "RESISTOR0402-RES"))
    )
    (comp (ref "R405")
      (value "10K/0.1%")
      (footprint "eagle-import:0402-RES")
      (fields (field (name "PARTNO") "ERA-2AEB103X"))
      (libsource (lib "eagle-import") (part "RESISTOR0402-RES"))
    )
    (comp (ref "R406")
      (value "10K/0.1%")
      (footprint "eagle-import:0402-RES")
      (fields (field (name "PARTNO") "ERA-2AEB103X"))
      (libsource (lib "eagle-import") (part "RESISTOR0402-RES"))
    )
    (comp (ref "R407")
      (value "120R")
      (footprint "eagle-import:0402-RES")
      (fields (field (name "PARTNO") "RC0402FR-07120RL"))
      (libsource (lib "eagle-import") (part "RESISTOR0402-RES"))
    )
    (comp (ref "R408")
      (value "120R")
      (footprint "eagle-import:0402-RES")
      (fields (field (name "PARTNO") "RC0402FR-07120RL"))
      (libsource (lib "eagle-import") (part "RESISTOR0402-RES"))
    )
    (comp (ref "SJ401")
      (value "SOLDERJUMPERNC2")
      (footprint "eagle-import:SJ_2S-NOTRACE")
      (libsource (lib "eagle-import") (part "SOLDERJUMPERNC2"))
    )
    (comp (ref "SJ402")
      (value "SOLDERJUMPERNC2")
      (footprint "eagle-import:SJ_2S-NOTRACE")
      (libsource (lib "eagle-import") (part "SOLDERJUMPERNC2"))
    )
    (comp (ref "U$401")
      (value "PESD0402-140")
      (footprint "eagle-import:0402-TVS")
      (libsource (lib "eagle-import") (part "DIODE-TVS"))
    )
    (comp (ref "U$402")
      (value "PESD0402-140")
      (footprint "eagle-import:0402-TVS")
      (libsource (lib "eagle-import") (part "DIODE-TVS"))
    )
    (comp (ref "U401")
      (value "MAX3051")
      (footprint "eagle-import:SOT23-8")
      (fields (field (name "PARTNO") "MAX3051EKA"))
      (libsource (lib "eagle-import") (part "MAX3051MAX3051EKA"))
    )
    (comp (ref "U402")
      (value "MAX3051")
      (footprint "eagle-import:SOT23-8")
      (fields (field (name "PARTNO") "MAX3051EKA"))
      (libsource (lib "eagle-import") (part "MAX3051MAX3051EKA"))
    )
    (comp (ref "C701")
      (value "2u2")
      (footprint "eagle-import:0603-CAP")
      (fields (field (name "PARTNO") "C1608Y5V1C225Z"))
      (libsource (lib "eagle-import") (part "CAP0603"))
    )
    (comp (ref "C702")
      (value "1u0")
      (footprint "eagle-import:0603-CAP")
      (fields (field (name "PARTNO") "CC0603ZRY5V7BB105"))
      (libsource (lib "eagle-import") (part "CAP0603"))
    )
    (comp (ref "C703")
      (value "10n")
      (footprint "eagle-import:0402-CAP")
      (fields (field (name "PARTNO") "CC0402KRX7R7BB103"))
      (libsource (lib "eagle-import") (part "CAP0402"))
    )
    (comp (ref "C704")
      (value "10n")
      (footprint "eagle-import:0402-CAP")
      (fields (field (name "PARTNO") "CC0402KRX7R7BB103"))
      (libsource (lib "eagle-import") (part "CAP0402"))
    )
    (comp (ref "C705")
      (value "1u0")
      (footprint "eagle-import:0603-CAP")
      (fields (field (name "PARTNO") "CC0603ZRY5V7BB105"))
      (libsource (lib "eagle-import") (part "CAP0603"))
    )
    (comp (ref "C706")
      (value "10u/10V")
      (footprint "eagle-import:0805-CAP")
      (fields (field (name "PARTNO") "CC0805ZKY5V6BB106"))
      (libsource (lib "eagle-import") (part "CAP0805"))
    )
    (comp (ref "C707")
      (value "1u0")
      (footprint "eagle-import:0603-CAP")
      (fields (field (name "PARTNO") "CC0603ZRY5V7BB105"))
      (libsource (lib "eagle-import") (part "CAP0603"))
    )
    (comp (ref "C708")
      (value "1u0")
      (footprint "eagle-import:0603-CAP")
      (fields (field (name "PARTNO") "CC0603ZRY5V7BB105"))
      (libsource (lib "eagle-import") (part "CAP0603"))
    )
    (comp (ref "C709")
      (value "0u1")
      (footprint "eagle-import:0402-CAP")
      (fields (field (name "PARTNO") "CC0402ZRY5V7BB104"))
      (libsource (lib "eagle-import") (part "CAP0402"))
    )
    (comp (ref "C710")
      (value "0u1")
      (footprint "eagle-import:0402-CAP")
      (fields (field (name "PARTNO") "CC0402ZRY5V7BB104"))
      (libsource (lib "eagle-import") (part "CAP0402"))
    )
    (comp (ref "C711")
      (value "0u1")
      (footprint "eagle-import:0402-CAP")
      (fields (field (name "PARTNO") "CC0402ZRY5V7BB104"))
      (libsource (lib "eagle-import") (part "CAP0402"))
    )
    (comp (ref "C712")
      (value "0u1")
      (footprint "eagle-import:0402-CAP")
      (fields (field (name "PARTNO") "CC0402ZRY5V7BB104"))
      (libsource (lib "eagle-import") (part "CAP0402"))
    )
    (comp (ref "C713")
      (value "0u1")
      (footprint "eagle-import:0402-CAP")
      (fields (field (name "PARTNO") "CC0402ZRY5V7BB104"))
      (libsource (lib "eagle-import") (part "CAP0402"))
    )
    (comp (ref "C714")
      (value "0u1")
      (footprint "eagle-import:0402-CAP")
      (fields (field (name "PARTNO") "CC0402ZRY5V7BB104"))
      (libsource (lib "eagle-import") (part "CAP0402"))
    )
    (comp (ref "C715")
      (value "2u2")
      (footprint "eagle-import:0603-CAP")
      (fields (field (name "PARTNO") "C1608Y5V1C225Z"))
      (libsource (lib "eagle-import") (part "CAP0603"))
    )
    (comp (ref "C716")
      (value "0u1")
      (footprint "eagle-import:0402-CAP")
      (fields (field (name "PARTNO") "CC0402ZRY5V7BB104"))
      (libsource (lib "eagle-import") (part "CAP0402"))
    )
    (comp (ref "C717")
      (value "2u2")
      (footprint "eagle-import:0603-CAP")
      (fields (field (name "PARTNO") "C1608Y5V1C225Z"))
      (libsource (lib "eagle-import") (part "CAP0603"))
    )
    (comp (ref "D701")
      (value "DIODE-SCHOTTKY")
      (footprint "eagle-import:SOD-523")
      (fields (field (name "PARTNO") "MBRA140"))
      (libsource (lib "eagle-import") (part "DIODE-SCHOTTKY"))
    )
    (comp (ref "R701")
      (value "10K")
      (footprint "eagle-import:0402-RES")
      (fields (field (name "PARTNO") "RC0402FR-0710KL"))
      (libsource (lib "eagle-import") (part "RESISTOR0402-RES"))
    )
    (comp (ref "R702")
      (value "10K")
      (footprint "eagle-import:0402-RES")
      (fields (field (name "PARTNO") "RC0402FR-0710KL"))
      (libsource (lib "eagle-import") (part "RESISTOR0402-RES"))
    )
    (comp (ref "R703")
      (value "47K")
      (footprint "eagle-import:0402-RES")
      (fields (field (name "PARTNO") "RMCF0402FT47K"))
      (libsource (lib "eagle-import") (part "RESISTOR0402-RES"))
    )
    (comp (ref "R704")
      (value "10K")
      (footprint "eagle-import:0402-RES")
      (fields (field (name "PARTNO") "RC0402FR-0710KL"))
      (libsource (lib "eagle-import") (part "RESISTOR0402-RES"))
    )
    (comp (ref "R705")
      (value "10K")
      (footprint "eagle-import:0402-RES")
      (fields (field (name "PARTNO") "RC0402FR-0710KL"))
      (libsource (lib "eagle-import") (part "RESISTOR0402-RES"))
    )
    (comp (ref "R706")
      (value "1K")
      (footprint "eagle-import:0402-RES")
      (fields (field (name "PARTNO") "RC0402FR-071KL"))
      (libsource (lib "eagle-import") (part "RESISTOR0402-RES"))
    )
    (comp (ref "R707")
      (value "10K/0.1%")
      (footprint "eagle-import:0402-RES")
      (fields (field (name "PARTNO") "ERA-2AEB103X"))
      (libsource (lib "eagle-import") (part "RESISTOR0402-RES"))
    )
    (comp (ref "R708")
      (value "10K/0.1%")
      (footprint "eagle-import:0402-RES")
      (fields (field (name "PARTNO") "ERA-2AEB103X"))
      (libsource (lib "eagle-import") (part "RESISTOR0402-RES"))
    )
    (comp (ref "R709")
      (value "10K")
      (footprint "eagle-import:0402-RES")
      (fields (field (name "PARTNO") "RC0402FR-0710KL"))
      (libsource (lib "eagle-import") (part "RESISTOR0402-RES"))
    )
    (comp (ref "S701")
      (value "RESET")
      (footprint "eagle-import:EVQP7J01K")
      (fields (field (name "PARTNO") "EVQP7J01K"))
      (libsource (lib "eagle-import") (part "SWITCH-MOMENTARY-2"))
    )
    (comp (ref "U$701")
      (value "MIC5332")
      (footprint "eagle-import:MLF-8-EPAD")
      (fields (field (name "PARTNO") "MIC5332-SSYMT"))
      (libsource (lib "eagle-import") (part "MIC5332"))
    )
    (comp (ref "U$702")
      (value "MIC5332")
      (footprint "eagle-import:MLF-8-EPAD")
      (fields (field (name "PARTNO") "MIC5332-SSYMT"))
      (libsource (lib "eagle-import") (part "MIC5332"))
    )
    (comp (ref "U$703")
      (value "BQ24315")
      (footprint "eagle-import:QFN8-DSG")
      (fields (field (name "PARTNO") "BQ24315DSGR"))
      (libsource (lib "eagle-import") (part "BQ24315"))
    )
    (comp (ref "U$704")
      (value "MS621FE")
      (footprint "eagle-import:MS621FE")
      (libsource (lib "eagle-import") (part "MS621FE"))
    )
    (comp (ref "U101")
      (value "STM32F4X7VX")
      (footprint "eagle-import:TQFP100")
      (fields (field (name "PARTNO") "STM32F427VI"))
      (libsource (lib "eagle-import") (part "STM32F4X7VX"))
    )
    (comp (ref "J1001")
      (value "SERVO_HEADER-3X8")
      (footprint "eagle-import:3X8RA_SERVO")
      (fields (field (name "BOM") "EXCLUDE"))
      (libsource (lib "eagle-import") (part "SERVO_HEADER-3X8"))
    )
    (comp (ref "JP1001")
      (value "M01SMD-4.5X1.5")
      (footprint "eagle-import:PAD-1.5X4.5")
      (libsource (lib "eagle-import") (part "M01SMD-4.5X1.5"))
    )
    (comp (ref "JP1002")
      (value "M01SMD-4.5X1.5")
      (footprint "eagle-import:PAD-1.5X4.5")
      (libsource (lib "eagle-import") (part "M01SMD-4.5X1.5"))
    )
    (comp (ref "L1001")
      (value "NUF8402MN")
      (footprint "eagle-import:DFN16-THIN")
      (fields (field (name "PARTNO") "NUF8402MN"))
      (libsource (lib "eagle-import") (part "NUF8402MN"))
    )
    (comp (ref "R1001")
      (value "220R")
      (footprint "eagle-import:0402-RES")
      (fields (field (name "PARTNO") "RC0402FR-07220RL"))
      (libsource (lib "eagle-import") (part "RESISTOR0402-RES"))
    )
    (comp (ref "R1002")
      (value "220R")
      (footprint "eagle-import:0402-RES")
      (fields (field (name "PARTNO") "RC0402FR-07220RL"))
      (libsource (lib "eagle-import") (part "RESISTOR0402-RES"))
    )
    (comp (ref "JP1101")
      (value "FIDUCIAL1.5X3")
      (footprint "eagle-import:FIDUCIAL-1.5X3")
      (libsource (lib "eagle-import") (part "FIDUCIAL1.5X3"))
    )
    (comp (ref "JP1102")
      (value "FIDUCIAL1.5X3")
      (footprint "eagle-import:FIDUCIAL-1.5X3")
      (libsource (lib "eagle-import") (part "FIDUCIAL1.5X3"))
    )
    (comp (ref "JP1103")
      (value "FIDUCIAL1.5X3")
      (footprint "eagle-import:FIDUCIAL-1.5X3")
      (libsource (lib "eagle-import") (part "FIDUCIAL1.5X3"))
    )
    (comp (ref "JP1104")
      (value "FIDUCIAL1.5X3")
      (footprint "eagle-import:FIDUCIAL-1.5X3")
      (libsource (lib "eagle-import") (part "FIDUCIAL1.5X3"))
    )
    (comp (ref "JP1105")
      (value "M01PTH")
      (footprint "eagle-import:1X01")
      (libsource (lib "eagle-import") (part "M01PTH"))
    )
    (comp (ref "M3_MOUNT1101")
      (value "MOUNT-HOLE3.1MM")
      (footprint "eagle-import:MOUNT-HOLE3.1")
      (libsource (lib "eagle-import") (part "MOUNT-HOLE3.1MM"))
    )
    (comp (ref "M3_MOUNT1102")
      (value "MOUNT-HOLE3.1MM")
      (footprint "eagle-import:MOUNT-HOLE3.1")
      (libsource (lib "eagle-import") (part "MOUNT-HOLE3.1MM"))
    )
    (comp (ref "M3_MOUNT1103")
      (value "MOUNT-HOLE3.1MM")
      (footprint "eagle-import:MOUNT-HOLE3.1")
      (libsource (lib "eagle-import") (part "MOUNT-HOLE3.1MM"))
    )
    (comp (ref "M3_MOUNT1104")
      (value "MOUNT-HOLE3.1MM")
      (footprint "eagle-import:MOUNT-HOLE3.1")
      (libsource (lib "eagle-import") (part "MOUNT-HOLE3.1MM"))
    )
    (comp (ref "OSHW_LOGO")
      (value "OSHW-LOGOS")
      (footprint "eagle-import:OSHW-LOGO-S")
      (libsource (lib "eagle-import") (part "OSHW-LOGOS"))
    )
    (comp (ref "C101")
      (value "16p")
      (footprint "eagle-import:0402-CAP")
      (fields (field (name "PARTNO") "C1005C0G1H160"))
      (libsource (lib "eagle-import") (part "CAP0402"))
    )
    (comp (ref "C102")
      (value "16p")
      (footprint "eagle-import:0402-CAP")
      (fields (field (name "PARTNO") "C1005C0G1H160"))
      (libsource (lib "eagle-import") (part "CAP0402"))
    )
    (comp (ref "R101")
      (value "10K")
      (footprint "eagle-import:0402-RES")
      (fields (field (name "PARTNO") "RC0402FR-0710KL"))
      (libsource (lib "eagle-import") (part "RESISTOR0402-RES"))
    )
    (comp (ref "X101")
      (value "3.2x2.5 mm / 24 MHz / 30 ppm / 10pF")
      (footprint "eagle-import:OSCILLATOR-3.2X2.5")
      (fields (field (name "PARTNO") "ABM8G-24.000MHZ-4Y-T3"))
      (libsource (lib "eagle-import") (part "OSCILLATOR-3.2X2.5"))
    )
    (comp (ref "C201")
      (value "0u1")
      (footprint "eagle-import:0402-CAP")
      (fields (field (name "PARTNO") "CC0402ZRY5V7BB104"))
      (libsource (lib "eagle-import") (part "CAP0402"))
    )
    (comp (ref "JP201")
      (value "JUMPER-3SMD")
      (footprint "eagle-import:SJ_3")
      (libsource (lib "eagle-import") (part "JUMPER-3SMD"))
    )
    (comp (ref "JP202")
      (value "HEADER-3X1RA")
      (footprint "eagle-import:3X1RA")
      (libsource (lib "eagle-import") (part "HEADER-3X1RA"))
    )
    (comp (ref "JP203")
      (value "M03X22X3_SILK_SM")
      (footprint "eagle-import:2X3")
      (libsource (lib "eagle-import") (part "M03X22X3_SILK_SM"))
    )
    (comp (ref "JP204")
      (value "M03X22X3_SILK_SM")
      (footprint "eagle-import:2X3")
      (libsource (lib "eagle-import") (part "M03X22X3_SILK_SM"))
    )
    (comp (ref "JP205")
      (value "M03X22X3_SILK_SM")
      (footprint "eagle-import:2X3")
      (libsource (lib "eagle-import") (part "M03X22X3_SILK_SM"))
    )
    (comp (ref "L201")
      (value "NUF8402MN")
      (footprint "eagle-import:DFN16-THIN")
      (fields (field (name "PARTNO") "NUF8402MN"))
      (libsource (lib "eagle-import") (part "NUF8402MN"))
    )
    (comp (ref "L202")
      (value "NUF8402MN")
      (footprint "eagle-import:DFN16-THIN")
      (fields (field (name "PARTNO") "NUF8402MN"))
      (libsource (lib "eagle-import") (part "NUF8402MN"))
    )
    (comp (ref "L203")
      (value "KNH16C104DA5TS")
      (footprint "eagle-import:KYOCERA-KNH16-DA")
      (libsource (lib "eagle-import") (part "KNH16C104DA5TS"))
    )
    (comp (ref "R201")
      (value "120R")
      (footprint "eagle-import:0402-RES")
      (fields (field (name "PARTNO") "RC0402FR-07120RL"))
      (libsource (lib "eagle-import") (part "RESISTOR0402-RES"))
    )
    (comp (ref "R202")
      (value "120R")
      (footprint "eagle-import:0402-RES")
      (fields (field (name "PARTNO") "RC0402FR-07120RL"))
      (libsource (lib "eagle-import") (part "RESISTOR0402-RES"))
    )
    (comp (ref "R203")
      (value "10K")
      (footprint "eagle-import:0402-RES")
      (fields (field (name "PARTNO") "RC0402FR-0710KL"))
      (libsource (lib "eagle-import") (part "RESISTOR0402-RES"))
    )
    (comp (ref "R204")
      (value "10K")
      (footprint "eagle-import:0402-RES")
      (fields (field (name "PARTNO") "RC0402FR-0710KL"))
      (libsource (lib "eagle-import") (part "RESISTOR0402-RES"))
    )
    (comp (ref "U$201")
      (value "PESD0402-140")
      (footprint "eagle-import:0402-TVS")
      (libsource (lib "eagle-import") (part "DIODE-TVS"))
    )
    (comp (ref "U$202")
      (value "PESD0402-140")
      (footprint "eagle-import:0402-TVS")
      (libsource (lib "eagle-import") (part "DIODE-TVS"))
    )
    (comp (ref "U$203")
      (value "74LVC2G240")
      (footprint "eagle-import:VSSOP8")
      (libsource (lib "eagle-import") (part "74LVC2G240"))
    )
    (comp (ref "U$204")
      (value "PESD0402-140")
      (footprint "eagle-import:0402-TVS")
      (libsource (lib "eagle-import") (part "DIODE-TVS"))
    )
    (comp (ref "C601")
      (value "22uF")
      (footprint "eagle-import:1210")
      (fields (field (name "PARTNO") "C3225X7R1C226M250AC"))
      (libsource (lib "eagle-import") (part "22UF-16V-20%-(1210)"))
    )
    (comp (ref "C602")
      (value "0u1")
      (footprint "eagle-import:0402-CAP")
      (fields (field (name "PARTNO") "CC0402ZRY5V7BB104"))
      (libsource (lib "eagle-import") (part "CAP0402"))
    )
    (comp (ref "C603")
      (value "0u1")
      (footprint "eagle-import:0402-CAP")
      (fields (field (name "PARTNO") "CC0402ZRY5V7BB104"))
      (libsource (lib "eagle-import") (part "CAP0402"))
    )
    (comp (ref "C604")
      (value "22uF")
      (footprint "eagle-import:1210")
      (fields (field (name "PARTNO") "C3225X7R1C226M250AC"))
      (libsource (lib "eagle-import") (part "22UF-16V-20%-(1210)"))
    )
    (comp (ref "C605")
      (value "22uF")
      (footprint "eagle-import:1210")
      (fields (field (name "PARTNO") "C3225X7R1C226M250AC"))
      (libsource (lib "eagle-import") (part "22UF-16V-20%-(1210)"))
    )
    (comp (ref "C606")
      (value "22uF")
      (footprint "eagle-import:1210")
      (fields (field (name "PARTNO") "C3225X7R1C226M250AC"))
      (libsource (lib "eagle-import") (part "22UF-16V-20%-(1210)"))
    )
    (comp (ref "L$601")
      (value "IND_4X4_MULTI")
      (footprint "eagle-import:IND_4X4_MULTI")
      (fields (field (name "MANUFACTURER_PART_NUMBER") "XFL4020-222MEB"))
      (libsource (lib "eagle-import") (part "IND_4X4_MULTI"))
    )
    (comp (ref "U$601")
      (value "TPS6303X")
      (footprint "eagle-import:PWSON10")
      (fields (field (name "PARTNO") "TPS63061DSCT"))
      (libsource (lib "eagle-import") (part "TPS6303X"))
    )
    (comp (ref "C501")
      (value "10u/10V")
      (footprint "eagle-import:0805-CAP")
      (fields (field (name "PARTNO") "CC0805ZKY5V6BB106"))
      (libsource (lib "eagle-import") (part "CAP0805"))
    )
    (comp (ref "C502")
      (value "10n")
      (footprint "eagle-import:0402-CAP")
      (fields (field (name "PARTNO") "CC0402KRX7R7BB103"))
      (libsource (lib "eagle-import") (part "CAP0402"))
    )
    (comp (ref "C503")
      (value "0u1")
      (footprint "eagle-import:0402-CAP")
      (fields (field (name "PARTNO") "CC0402ZRY5V7BB104"))
      (libsource (lib "eagle-import") (part "CAP0402"))
    )
    (comp (ref "U$501")
      (value "MAX21100")
      (footprint "eagle-import:16LGA-3X3")
      (fields (field (name "PARTNO") "MAX21100+"))
      (libsource (lib "eagle-import") (part "MAX21100"))
    )
  )
  (nets
    (net (code "1") (name "ACCEL_DRDY") (class "Default")
      (node (ref "U$501") (pin "11") (pinfunction "INT1_11") (pintype "bidirectional"))
      (node (ref "U101") (pin "90") (pinfunction "PB4_90") (pintype "bidirectional"))
    )
    (net (code "2") (name "ALARM") (class "Default")
      (node (ref "U101") (pin "77") (pinfunction "PA15_77") (pintype "bidirectional"))
    )
    (net (code "3") (name "CAN1_H") (class "Default")
      (node (ref "JP405") (pin "2") (pinfunction "2_2") (pintype "passive"))
      (node (ref "R407") (pin "P$1") (pinfunction "1_P$1") (pintype "passive"))
      (node (ref "U402") (pin "7") (pinfunction "CANH_7") (pintype "bidirectional"))
    )
    (net (code "4") (name "CAN1_L") (class "Default")
      (node (ref "JP405") (pin "3") (pinfunction "3_3") (pintype "passive"))
      (node (ref "SJ402") (pin "2") (pinfunction "2_2") (pintype "passive"))
      (node (ref "U402") (pin "6") (pinfunction "CANL_6") (pintype "bidirectional"))
    )
    (net (code "5") (name "CAN1_RX") (class "Default")
      (node (ref "U101") (pin "81") (pinfunction "PD0_81") (pintype "bidirectional"))
      (node (ref "U402") (pin "4") (pinfunction "DOUT_4") (pintype "output"))
    )
    (net (code "6") (name "CAN1_TX") (class "Default")
      (node (ref "U101") (pin "82") (pinfunction "PD1_82") (pintype "bidirectional"))
      (node (ref "U402") (pin "1") (pinfunction "DIN_1") (pintype "input"))
    )
    (net (code "7") (name "CAN2_RX") (class "Default")
      (node (ref "U101") (pin "51") (pinfunction "PB12_51") (pintype "bidirectional"))
      (node (ref "U401") (pin "4") (pinfunction "DOUT_4") (pintype "output"))
    )
    (net (code "8") (name "CAN2_TX") (class "Default")
      (node (ref "U101") (pin "92") (pinfunction "PB6_92") (pintype "bidirectional"))
      (node (ref "U401") (pin "1") (pinfunction "DIN_1") (pintype "input"))
    )
    (net (code "9") (name "FMU-BOOT0") (class "Default")
      (node (ref "JP1105") (pin "1") (pinfunction "1_1") (pintype "passive"))
      (node (ref "R709") (pin "P$2") (pinfunction "2_P$2") (pintype "passive"))
      (node (ref "U101") (pin "94") (pinfunction "BOOT0_94") (pintype "input"))
    )
    (net (code "10") (name "FMU-CH1") (class "Default")
      (node (ref "L1001") (pin "P$4") (pinfunction "P$1_P$4") (pintype "bidirectional"))
      (node (ref "U101") (pin "45") (pinfunction "PE14_45") (pintype "bidirectional"))
    )
    (net (code "11") (name "FMU-CH2") (class "Default")
      (node (ref "L1001") (pin "P$5") (pinfunction "P$1_P$5") (pintype "bidirectional"))
      (node (ref "U101") (pin "44") (pinfunction "PE13_44") (pintype "bidirectional"))
    )
    (net (code "12") (name "FMU-CH3") (class "Default")
      (node (ref "L1001") (pin "P$6") (pinfunction "P$1_P$6") (pintype "bidirectional"))
      (node (ref "U101") (pin "42") (pinfunction "PE11_42") (pintype "bidirectional"))
    )
    (net (code "13") (name "FMU-CH4") (class "Default")
      (node (ref "L1001") (pin "P$7") (pinfunction "P$1_P$7") (pintype "bidirectional"))
      (node (ref "U101") (pin "40") (pinfunction "PE9_40") (pintype "bidirectional"))
    )
    (net (code "14") (name "FMU-CH5") (class "Default")
      (node (ref "L1001") (pin "P$2") (pinfunction "P$1_P$2") (pintype "bidirectional"))
      (node (ref "U101") (pin "60") (pinfunction "PD13_60") (pintype "bidirectional"))
    )
    (net (code "15") (name "FMU-CH6") (class "Default")
      (node (ref "L1001") (pin "P$3") (pinfunction "P$1_P$3") (pintype "bidirectional"))
      (node (ref "U101") (pin "62") (pinfunction "PD15_62") (pintype "bidirectional"))
    )
    (net (code "16") (name "FMU-CH7") (class "Default")
      (node (ref "L1001") (pin "P$8") (pinfunction "P$1_P$8") (pintype "bidirectional"))
      (node (ref "U101") (pin "24") (pinfunction "PA1_24") (pintype "bidirectional"))
    )
    (net (code "17") (name "FMU-CH8") (class "Default")
      (node (ref "L1001") (pin "P$1") (pinfunction "P$1_P$1") (pintype "bidirectional"))
      (node (ref "U$203") (pin "3") (pinfunction "2Y_3") (pintype "bidirectional"))
      (node (ref "U101") (pin "61") (pinfunction "PD14_61") (pintype "bidirectional"))
    )
    (net (code "18") (name "FMU-CH9") (class "Default")
      (node (ref "R1001") (pin "P$2") (pinfunction "2_P$2") (pintype "passive"))
      (node (ref "U101") (pin "25") (pinfunction "PA2_25") (pintype "bidirectional"))
    )
    (net (code "19") (name "FMU-CH10") (class "Default")
      (node (ref "R1002") (pin "P$2") (pinfunction "2_P$2") (pintype "passive"))
      (node (ref "U101") (pin "26") (pinfunction "PA3_26") (pintype "bidirectional"))
    )
    (net (code "20") (name "FMU-I2C1_SCL") (class "Default")
      (node (ref "L403") (pin "P$2") (pinfunction "P$1_P$2") (pintype "bidirectional"))
      (node (ref "R402") (pin "P$1") (pinfunction "1_P$1") (pintype "passive"))
      (node (ref "U101") (pin "95") (pinfunction "PB8_95") (pintype "bidirectional"))
    )
    (net (code "21") (name "FMU-I2C1_SDA") (class "Default")
      (node (ref "L403") (pin "P$7") (pinfunction "P$1_P$7") (pintype "bidirectional"))
      (node (ref "R404") (pin "P$1") (pinfunction "1_P$1") (pintype "passive"))
      (node (ref "U101") (pin "96") (pinfunction "PB9_96") (pintype "bidirectional"))
    )
    (net (code "22") (name "FMU-I2C2_SCL") (class "Default")
      (node (ref "L403") (pin "P$4") (pinfunction "P$1_P$4") (pintype "bidirectional"))
      (node (ref "R401") (pin "P$1") (pinfunction "1_P$1") (pintype "passive"))
      (node (ref "U101") (pin "47") (pinfunction "PB10_47") (pintype "bidirectional"))
    )
    (net (code "23") (name "FMU-I2C2_SDA") (class "Default")
      (node (ref "L403") (pin "P$8") (pinfunction "P$1_P$8") (pintype "bidirectional"))
      (node (ref "R403") (pin "P$1") (pinfunction "1_P$1") (pintype "passive"))
      (node (ref "U101") (pin "48") (pinfunction "PB11_48") (pintype "bidirectional"))
    )
    (net (code "24") (name "FMU-LED_SAFETY") (class "Default")
      (node (ref "R801") (pin "P$2") (pinfunction "2_P$2") (pintype "passive"))
      (node (ref "U101") (pin "9") (pinfunction "PC15_9") (pintype "bidirectional"))
    )
    (net (code "25") (name "FMU-SWCLK") (class "Default")
      (node (ref "JX301") (pin "4") (pinfunction "S_4") (pintype "passive"))
      (node (ref "TP2") (pin "TP") (pinfunction "TP_TP") (pintype "input"))
      (node (ref "U101") (pin "76") (pinfunction "PA14_76") (pintype "bidirectional"))
    )
    (net (code "26") (name "FMU-SWDIO") (class "Default")
      (node (ref "JX301") (pin "2") (pinfunction "S_2") (pintype "passive"))
      (node (ref "TP1") (pin "TP") (pinfunction "TP_TP") (pintype "input"))
      (node (ref "U101") (pin "72") (pinfunction "PA13_72") (pintype "bidirectional"))
    )
    (net (code "27") (name "FMU-SWO") (class "Default")
      (node (ref "JX301") (pin "6") (pinfunction "S_6") (pintype "passive"))
      (node (ref "TP3") (pin "TP") (pinfunction "TP_TP") (pintype "input"))
      (node (ref "U101") (pin "89") (pinfunction "PB3_89") (pintype "bidirectional"))
    )
    (net (code "28") (name "FMU-UART7_RX") (class "Default")
      (node (ref "L202") (pin "P$8") (pinfunction "P$1_P$8") (pintype "bidirectional"))
      (node (ref "U101") (pin "38") (pinfunction "PE7_38") (pintype "bidirectional"))
    )
    (net (code "29") (name "FMU-UART7_TX") (class "Default")
      (node (ref "L202") (pin "P$6") (pinfunction "P$1_P$6") (pintype "bidirectional"))
      (node (ref "U101") (pin "39") (pinfunction "PE8_39") (pintype "bidirectional"))
    )
    (net (code "30") (name "FMU-UART8_RX") (class "Default")
      (node (ref "U$203") (pin "6") (pinfunction "1Y_6") (pintype "bidirectional"))
      (node (ref "U101") (pin "97") (pinfunction "PE0_97") (pintype "bidirectional"))
    )
    (net (code "31") (name "FMU-UART8_TX") (class "Default")
      (node (ref "U$203") (pin "5") (pinfunction "2A_5") (pintype "bidirectional"))
      (node (ref "U101") (pin "98") (pinfunction "PE1_98") (pintype "bidirectional"))
    )
    (net (code "32") (name "FMU-USART2_CTS") (class "Default")
      (node (ref "L201") (pin "P$1") (pinfunction "P$1_P$1") (pintype "bidirectional"))
      (node (ref "U101") (pin "84") (pinfunction "PD3_84") (pintype "bidirectional"))
    )
    (net (code "33") (name "FMU-USART2_RTS") (class "Default")
      (node (ref "L201") (pin "P$2") (pinfunction "P$1_P$2") (pintype "bidirectional"))
      (node (ref "U101") (pin "85") (pinfunction "PD4_85") (pintype "bidirectional"))
    )
    (net (code "34") (name "FMU-USART2_RX") (class "Default")
      (node (ref "L201") (pin "P$4") (pinfunction "P$1_P$4") (pintype "bidirectional"))
      (node (ref "U101") (pin "87") (pinfunction "PD6_87") (pintype "bidirectional"))
    )
    (net (code "35") (name "FMU-USART2_TX") (class "Default")
      (node (ref "L201") (pin "P$3") (pinfunction "P$1_P$3") (pintype "bidirectional"))
      (node (ref "U101") (pin "86") (pinfunction "PD5_86") (pintype "bidirectional"))
    )
    (net (code "36") (name "FMU-USART3_CTS") (class "Default")
      (node (ref "L201") (pin "P$7") (pinfunction "P$1_P$7") (pintype "bidirectional"))
      (node (ref "U101") (pin "58") (pinfunction "PD11_58") (pintype "bidirectional"))
    )
    (net (code "37") (name "FMU-USART3_RTS") (class "Default")
      (node (ref "L201") (pin "P$8") (pinfunction "P$1_P$8") (pintype "bidirectional"))
      (node (ref "U101") (pin "59") (pinfunction "PD12_59") (pintype "bidirectional"))
    )
    (net (code "38") (name "FMU-USART3_RX") (class "Default")
      (node (ref "L201") (pin "P$6") (pinfunction "P$1_P$6") (pintype "bidirectional"))
      (node (ref "U101") (pin "56") (pinfunction "PD9_56") (pintype "bidirectional"))
    )
    (net (code "39") (name "FMU-USART3_TX") (class "Default")
      (node (ref "L201") (pin "P$5") (pinfunction "P$1_P$5") (pintype "bidirectional"))
      (node (ref "U101") (pin "55") (pinfunction "PD8_55") (pintype "bidirectional"))
    )
    (net (code "40") (name "FMU-VDD_3V3") (class "Default")
      (node (ref "C201") (pin "P$1") (pinfunction "1_P$1") (pintype "passive"))
      (node (ref "C301") (pin "P$1") (pinfunction "1_P$1") (pintype "passive"))
      (node (ref "C302") (pin "P$1") (pinfunction "1_P$1") (pintype "passive"))
      (node (ref "C401") (pin "P$1") (pinfunction "1_P$1") (pintype "passive"))
      (node (ref "C402") (pin "P$1") (pinfunction "1_P$1") (pintype "passive"))
      (node (ref "C705") (pin "P$1") (pinfunction "1_P$1") (pintype "passive"))
      (node (ref "C706") (pin "P$1") (pinfunction "1_P$1") (pintype "passive"))
      (node (ref "C709") (pin "P$1") (pinfunction "1_P$1") (pintype "passive"))
      (node (ref "C710") (pin "P$1") (pinfunction "1_P$1") (pintype "passive"))
      (node (ref "C711") (pin "P$1") (pinfunction "1_P$1") (pintype "passive"))
      (node (ref "C712") (pin "P$1") (pinfunction "1_P$1") (pintype "passive"))
      (node (ref "C714") (pin "P$1") (pinfunction "1_P$1") (pintype "passive"))
      (node (ref "C716") (pin "P$1") (pinfunction "1_P$1") (pintype "passive"))
      (node (ref "D701") (pin "A") (pinfunction "A_A") (pintype "passive"))
      (node (ref "JP801") (pin "1") (pinfunction "1_1") (pintype "passive"))
      (node (ref "JX301") (pin "1") (pinfunction "S_1") (pintype "passive"))
      (node (ref "R401") (pin "P$2") (pinfunction "2_P$2") (pintype "passive"))
      (node (ref "R402") (pin "P$2") (pinfunction "2_P$2") (pintype "passive"))
      (node (ref "R403") (pin "P$2") (pinfunction "2_P$2") (pintype "passive"))
      (node (ref "R404") (pin "P$2") (pinfunction "2_P$2") (pintype "passive"))
      (node (ref "R702") (pin "P$1") (pinfunction "1_P$1") (pintype "passive"))
      (node (ref "R704") (pin "P$1") (pinfunction "1_P$1") (pintype "passive"))
      (node (ref "R705") (pin "P$1") (pinfunction "1_P$1") (pintype "passive"))
      (node (ref "TP5") (pin "TP") (pinfunction "TP_TP") (pintype "input"))
      (node (ref "U$203") (pin "8") (pinfunction "VCC_8") (pintype "power_in"))
      (node (ref "U$302") (pin "3") (pinfunction "~{WP}/IO2_3") (pintype "bidirectional"))
      (node (ref "U$302") (pin "7") (pinfunction "~{HOLD}/IO3_7") (pintype "bidirectional"))
      (node (ref "U$302") (pin "8") (pinfunction "VCC_8") (pintype "bidirectional"))
      (node (ref "U$701") (pin "7") (pinfunction "VOUT2_7") (pintype "bidirectional"))
      (node (ref "U$801") (pin "C") (pinfunction "C_C") (pintype "passive"))
      (node (ref "U101") (pin "100") (pinfunction "VDD_100") (pintype "power_in"))
      (node (ref "U101") (pin "11") (pinfunction "VDD_11") (pintype "power_in"))
      (node (ref "U101") (pin "19") (pinfunction "VDD_19") (pintype "power_in"))
      (node (ref "U101") (pin "21") (pinfunction "VREF+_21") (pintype "input"))
      (node (ref "U101") (pin "22") (pinfunction "VDDA_22") (pintype "power_in"))
      (node (ref "U101") (pin "28") (pinfunction "VDD_28") (pintype "power_in"))
      (node (ref "U101") (pin "50") (pinfunction "VDD_50") (pintype "power_in"))
      (node (ref "U101") (pin "75") (pinfunction "VDD_75") (pintype "power_in"))
      (node (ref "U401") (pin "3") (pinfunction "VCC_3") (pintype "input"))
      (node (ref "U402") (pin "3") (pinfunction "VCC_3") (pintype "input"))
    )
    (net (code "41") (name "FMU-~{RESET}") (class "Default")
      (node (ref "C713") (pin "P$2") (pinfunction "2_P$2") (pintype "passive"))
      (node (ref "JX301") (pin "10") (pinfunction "S_10") (pintype "passive"))
      (node (ref "S701") (pin "A1") (pinfunction "1_A1") (pintype "passive"))
      (node (ref "TP4") (pin "TP") (pinfunction "TP_TP") (pintype "input"))
      (node (ref "U$701") (pin "3") (pinfunction "POR2_3") (pintype "bidirectional"))
      (node (ref "U101") (pin "14") (pinfunction "NRST_14") (pintype "input"))
    )
    (net (code "42") (name "FMU_AUX_ADC1") (class "Default")
      (node (ref "R405") (pin "P$1") (pinfunction "1_P$1") (pintype "passive"))
      (node (ref "U101") (pin "18") (pinfunction "PC3_18") (pintype "bidirectional"))
    )
    (net (code "43") (name "FMU_AUX_ADC2") (class "Default")
      (node (ref "R406") (pin "P$1") (pinfunction "1_P$1") (pintype "passive"))
      (node (ref "U101") (pin "33") (pinfunction "PC4_33") (pintype "bidirectional"))
    )
    (net (code "44") (name "FRAM_MISO") (class "Default")
      (node (ref "U$302") (pin "2") (pinfunction "DO/IO1_2") (pintype "bidirectional"))
      (node (ref "U101") (pin "53") (pinfunction "PB14_53") (pintype "bidirectional"))
    )
    (net (code "45") (name "FRAM_MOSI") (class "Default")
      (node (ref "U$302") (pin "5") (pinfunction "DI/IO0_5") (pintype "bidirectional"))
      (node (ref "U101") (pin "54") (pinfunction "PB15_54") (pintype "bidirectional"))
    )
    (net (code "46") (name "FRAM_SCK") (class "Default")
      (node (ref "U$302") (pin "6") (pinfunction "CLK_6") (pintype "bidirectional"))
      (node (ref "U101") (pin "52") (pinfunction "PB13_52") (pintype "bidirectional"))
    )
    (net (code "47") (name "GND") (class "Default")
      (node (ref "C101") (pin "P$2") (pinfunction "2_P$2") (pintype "passive"))
      (node (ref "C102") (pin "P$1") (pinfunction "1_P$1") (pintype "passive"))
      (node (ref "C201") (pin "P$2") (pinfunction "2_P$2") (pintype "passive"))
      (node (ref "C301") (pin "P$2") (pinfunction "2_P$2") (pintype "passive"))
      (node (ref "C302") (pin "P$2") (pinfunction "2_P$2") (pintype "passive"))
      (node (ref "C401") (pin "P$2") (pinfunction "2_P$2") (pintype "passive"))
      (node (ref "C402") (pin "P$2") (pinfunction "2_P$2") (pintype "passive"))
      (node (ref "C403") (pin "P$2") (pinfunction "2_P$2") (pintype "passive"))
      (node (ref "C404") (pin "P$2") (pinfunction "2_P$2") (pintype "passive"))
      (node (ref "C501") (pin "P$2") (pinfunction "2_P$2") (pintype "passive"))
      (node (ref "C502") (pin "P$2") (pinfunction "2_P$2") (pintype "passive"))
      (node (ref "C503") (pin "P$2") (pinfunction "2_P$2") (pintype "passive"))
      (node (ref "C601") (pin "2") (pinfunction "2_2") (pintype "passive"))
      (node (ref "C602") (pin "P$2") (pinfunction "2_P$2") (pintype "passive"))
      (node (ref "C603") (pin "P$2") (pinfunction "2_P$2") (pintype "passive"))
      (node (ref "C604") (pin "2") (pinfunction "2_2") (pintype "passive"))
      (node (ref "C605") (pin "2") (pinfunction "2_2") (pintype "passive"))
      (node (ref "C606") (pin "2") (pinfunction "2_2") (pintype "passive"))
      (node (ref "C701") (pin "P$2") (pinfunction "2_P$2") (pintype "passive"))
      (node (ref "C702") (pin "P$2") (pinfunction "2_P$2") (pintype "passive"))
      (node (ref "C703") (pin "P$1") (pinfunction "1_P$1") (pintype "passive"))
      (node (ref "C704") (pin "P$2") (pinfunction "2_P$2") (pintype "passive"))
      (node (ref "C705") (pin "P$2") (pinfunction "2_P$2") (pintype "passive"))
      (node (ref "C706") (pin "P$2") (pinfunction "2_P$2") (pintype "passive"))
      (node (ref "C707") (pin "P$2") (pinfunction "2_P$2") (pintype "passive"))
      (node (ref "C708") (pin "P$2") (pinfunction "2_P$2") (pintype "passive"))
      (node (ref "C709") (pin "P$2") (pinfunction "2_P$2") (pintype "passive"))
      (node (ref "C710") (pin "P$2") (pinfunction "2_P$2") (pintype "passive"))
      (node (ref "C711") (pin "P$2") (pinfunction "2_P$2") (pintype "passive"))
      (node (ref "C712") (pin "P$2") (pinfunction "2_P$2") (pintype "passive"))
      (node (ref "C713") (pin "P$1") (pinfunction "1_P$1") (pintype "passive"))
      (node (ref "C714") (pin "P$2") (pinfunction "2_P$2") (pintype "passive"))
      (node (ref "C715") (pin "P$2") (pinfunction "2_P$2") (pintype "passive"))
      (node (ref "C716") (pin "P$2") (pinfunction "2_P$2") (pintype "passive"))
      (node (ref "C717") (pin "P$2") (pinfunction "2_P$2") (pintype "passive"))
      (node (ref "D901") (pin "A") (pinfunction "A_A") (pintype "passive"))
      (node (ref "J1001") (pin "GND_S1") (pinfunction "S_GND_S1") (pintype "passive"))
      (node (ref "J1001") (pin "GND_S2") (pinfunction "S_GND_S2") (pintype "passive"))
      (node (ref "J1001") (pin "GND_S3") (pinfunction "S_GND_S3") (pintype "passive"))
      (node (ref "J1001") (pin "GND_S4") (pinfunction "S_GND_S4") (pintype "passive"))
      (node (ref "J1001") (pin "GND_S5") (pinfunction "S_GND_S5") (pintype "passive"))
      (node (ref "J1001") (pin "GND_S6") (pinfunction "S_GND_S6") (pintype "passive"))
      (node (ref "J1001") (pin "GND_S7") (pinfunction "S_GND_S7") (pintype "passive"))
      (node (ref "J1001") (pin "GND_S8") (pinfunction "S_GND_S8") (pintype "passive"))
      (node (ref "J401") (pin "7") (pinfunction "7_7") (pintype "passive"))
      (node (ref "JP202") (pin "3") (pinfunction "3_3") (pintype "bidirectional"))
      (node (ref "JP203") (pin "5") (pinfunction "5_5") (pintype "bidirectional"))
      (node (ref "JP204") (pin "5") (pinfunction "5_5") (pintype "bidirectional"))
      (node (ref "JP205") (pin "5") (pinfunction "5_5") (pintype "bidirectional"))
      (node (ref "JP301") (pin "4") (pinfunction "4_4") (pintype "passive"))
      (node (ref "JP401") (pin "4") (pinfunction "4_4") (pintype "passive"))
      (node (ref "JP402") (pin "4") (pinfunction "4_4") (pintype "passive"))
      (node (ref "JP403") (pin "3") (pinfunction "3_3") (pintype "passive"))
      (node (ref "JP404") (pin "4") (pinfunction "4_4") (pintype "passive"))
      (node (ref "JP405") (pin "4") (pinfunction "4_4") (pintype "passive"))
      (node (ref "JP901") (pin "2") (pinfunction "2_2") (pintype "passive"))
      (node (ref "JX301") (pin "3") (pinfunction "S_3") (pintype "passive"))
      (node (ref "JX301") (pin "5") (pinfunction "S_5") (pintype "passive"))
      (node (ref "JX301") (pin "9") (pinfunction "S_9") (pintype "passive"))
      (node (ref "L1001") (pin "P$EP") (pinfunction "GND_P$EP") (pintype "power_in"))
      (node (ref "L201") (pin "P$EP") (pinfunction "GND_P$EP") (pintype "power_in"))
      (node (ref "L202") (pin "P$EP") (pinfunction "GND_P$EP") (pintype "power_in"))
      (node (ref "L203") (pin "P$3") (pinfunction "P$3_P$3") (pintype "bidirectional"))
      (node (ref "L203") (pin "P$4") (pinfunction "P$3_P$4") (pintype "bidirectional"))
      (node (ref "L203") (pin "P$5") (pinfunction "P$3_P$5") (pintype "bidirectional"))
      (node (ref "L401") (pin "P$3") (pinfunction "P$3_P$3") (pintype "bidirectional"))
      (node (ref "L401") (pin "P$4") (pinfunction "P$3_P$4") (pintype "bidirectional"))
      (node (ref "L401") (pin "P$5") (pinfunction "P$3_P$5") (pintype "bidirectional"))
      (node (ref "L402") (pin "P$3") (pinfunction "P$3_P$3") (pintype "bidirectional"))
      (node (ref "L402") (pin "P$4") (pinfunction "P$3_P$4") (pintype "bidirectional"))
      (node (ref "L402") (pin "P$5") (pinfunction "P$3_P$5") (pintype "bidirectional"))
      (node (ref "L403") (pin "P$1") (pinfunction "P$1_P$1") (pintype "bidirectional"))
      (node (ref "L403") (pin "P$11") (pinfunction "P$2_P$11") (pintype "bidirectional"))
      (node (ref "L403") (pin "P$12") (pinfunction "P$2_P$12") (pintype "bidirectional"))
      (node (ref "L403") (pin "P$14") (pinfunction "P$2_P$14") (pintype "bidirectional"))
      (node (ref "L403") (pin "P$16") (pinfunction "P$2_P$16") (pintype "bidirectional"))
      (node (ref "L403") (pin "P$3") (pinfunction "P$1_P$3") (pintype "bidirectional"))
      (node (ref "L403") (pin "P$5") (pinfunction "P$1_P$5") (pintype "bidirectional"))
      (node (ref "L403") (pin "P$6") (pinfunction "P$1_P$6") (pintype "bidirectional"))
      (node (ref "L403") (pin "P$EP") (pinfunction "GND_P$EP") (pintype "power_in"))
      (node (ref "L404") (pin "P$3") (pinfunction "P$3_P$3") (pintype "bidirectional"))
      (node (ref "L404") (pin "P$4") (pinfunction "P$3_P$4") (pintype "bidirectional"))
      (node (ref "L404") (pin "P$5") (pinfunction "P$3_P$5") (pintype "bidirectional"))
      (node (ref "R101") (pin "P$2") (pinfunction "2_P$2") (pintype "passive"))
      (node (ref "R203") (pin "P$2") (pinfunction "2_P$2") (pintype "passive"))
      (node (ref "R204") (pin "P$1") (pinfunction "1_P$1") (pintype "passive"))
      (node (ref "R701") (pin "P$1") (pinfunction "1_P$1") (pintype "passive"))
      (node (ref "R703") (pin "P$2") (pinfunction "2_P$2") (pintype "passive"))
      (node (ref "R708") (pin "P$2") (pinfunction "2_P$2") (pintype "passive"))
      (node (ref "R709") (pin "P$1") (pinfunction "1_P$1") (pintype "passive"))
      (node (ref "R802") (pin "P$2") (pinfunction "2_P$2") (pintype "passive"))
      (node (ref "R805") (pin "P$1") (pinfunction "1_P$1") (pintype "passive"))
      (node (ref "R903") (pin "P$1") (pinfunction "1_P$1") (pintype "passive"))
      (node (ref "S701") (pin "B3") (pinfunction "2_B3") (pintype "passive"))
      (node (ref "U$201") (pin "A") (pinfunction "A_A") (pintype "passive"))
      (node (ref "U$202") (pin "A") (pinfunction "A_A") (pintype "passive"))
      (node (ref "U$203") (pin "1") (pinfunction "~{1OE}_1") (pintype "input"))
      (node (ref "U$203") (pin "4") (pinfunction "GND_4") (pintype "power_in"))
      (node (ref "U$204") (pin "A") (pinfunction "A_A") (pintype "passive"))
      (node (ref "U$301") (pin "2") (pinfunction "GND_2") (pintype "bidirectional"))
      (node (ref "U$302") (pin "4") (pinfunction "GND_4") (pintype "bidirectional"))
      (node (ref "U$302") (pin "PAD") (pinfunction "GND_PAD") (pintype "bidirectional"))
      (node (ref "U$401") (pin "A") (pinfunction "A_A") (pintype "passive"))
      (node (ref "U$402") (pin "A") (pinfunction "A_A") (pintype "passive"))
      (node (ref "U$501") (pin "10") (pinfunction "RSV1_10") (pintype "input"))
      (node (ref "U$501") (pin "5") (pinfunction "GND_5") (pintype "power_in"))
      (node (ref "U$601") (pin "11") (pinfunction "GND_11") (pintype "power_in"))
      (node (ref "U$601") (pin "15") (pinfunction "PGND_15") (pintype "power_in"))
      (node (ref "U$601") (pin "16") (pinfunction "PGND_16") (pintype "power_in"))
      (node (ref "U$601") (pin "17") (pinfunction "PGND_17") (pintype "power_in"))
      (node (ref "U$601") (pin "18") (pinfunction "PGND_18") (pintype "power_in"))
      (node (ref "U$601") (pin "19") (pinfunction "PGND_19") (pintype "power_in"))
      (node (ref "U$601") (pin "20") (pinfunction "PGND_20") (pintype "power_in"))
      (node (ref "U$601") (pin "21") (pinfunction "PGND_21") (pintype "power_in"))
      (node (ref "U$601") (pin "22") (pinfunction "PGND_22") (pintype "power_in"))
      (node (ref "U$601") (pin "23") (pinfunction "PGND_23") (pintype "power_in"))
      (node (ref "U$601") (pin "4") (pinfunction "PS/SYNC_4") (pintype "input"))
      (node (ref "U$601") (pin "6") (pinfunction "PGND_6") (pintype "power_in"))
      (node (ref "U$601") (pin "7") (pinfunction "PGND_7") (pintype "power_in"))
      (node (ref "U$601") (pin "8") (pinfunction "PGND_8") (pintype "power_in"))
      (node (ref "U$601") (pin "9") (pinfunction "PGND_9") (pintype "power_in"))
      (node (ref "U$601") (pin "EP") (pinfunction "PGND_EP") (pintype "power_in"))
      (node (ref "U$601") (pin "EP1") (pinfunction "PGND_EP1") (pintype "power_in"))
      (node (ref "U$701") (pin "2") (pinfunction "GND_2") (pintype "bidirectional"))
      (node (ref "U$701") (pin "GND") (pinfunction "GND_GND") (pintype "bidirectional"))
      (node (ref "U$702") (pin "2") (pinfunction "GND_2") (pintype "bidirectional"))
      (node (ref "U$702") (pin "4") (pinfunction "EN2_4") (pintype "bidirectional"))
      (node (ref "U$702") (pin "GND") (pinfunction "GND_GND") (pintype "bidirectional"))
      (node (ref "U$703") (pin "2") (pinfunction "VSS_2") (pintype "bidirectional"))
      (node (ref "U$703") (pin "6") (pinfunction "VBAT_6") (pintype "bidirectional"))
      (node (ref "U$703") (pin "GND") (pinfunction "VSS_GND") (pintype "bidirectional"))
      (node (ref "U$703") (pin "P$2") (pinfunction "VSS_P$2") (pintype "bidirectional"))
      (node (ref "U$703") (pin "P$3") (pinfunction "VSS_P$3") (pintype "bidirectional"))
      (node (ref "U$704") (pin "2") (pinfunction "NEG_2") (pintype "bidirectional"))
      (node (ref "U$801") (pin "A") (pinfunction "A_A") (pintype "passive"))
      (node (ref "U101") (pin "10") (pinfunction "VSS_10") (pintype "power_in"))
      (node (ref "U101") (pin "20") (pinfunction "VSSA_20") (pintype "power_in"))
      (node (ref "U101") (pin "27") (pinfunction "VSS_27") (pintype "power_in"))
      (node (ref "U101") (pin "74") (pinfunction "VSS_74") (pintype "power_in"))
      (node (ref "U101") (pin "99") (pinfunction "VSS_99") (pintype "power_in"))
      (node (ref "U401") (pin "2") (pinfunction "GND_2") (pintype "power_in"))
      (node (ref "U401") (pin "5") (pinfunction "SHDN_5") (pintype "input"))
      (node (ref "U401") (pin "8") (pinfunction "RS_8") (pintype "input"))
      (node (ref "U402") (pin "2") (pinfunction "GND_2") (pintype "power_in"))
      (node (ref "U402") (pin "5") (pinfunction "SHDN_5") (pintype "input"))
      (node (ref "U402") (pin "8") (pinfunction "RS_8") (pintype "input"))
      (node (ref "X101") (pin "2") (pinfunction "NC_2_2") (pintype "power_in"))
      (node (ref "X101") (pin "4") (pinfunction "NC_4_4") (pintype "power_in"))
    )
    (net (code "48") (name "GPIO_EXT_1") (class "Default")
      (node (ref "J401") (pin "5") (pinfunction "5_5") (pintype "passive"))
      (node (ref "U101") (pin "8") (pinfunction "PC14_8") (pintype "bidirectional"))
    )
    (net (code "49") (name "GYRO_DRDY") (class "Default")
      (node (ref "U$501") (pin "9") (pinfunction "INT2_9") (pintype "bidirectional"))
      (node (ref "U101") (pin "35") (pinfunction "PB0_35") (pintype "bidirectional"))
    )
    (net (code "50") (name "IO-~{RESET}") (class "Default")
      (node (ref "U$702") (pin "3") (pinfunction "POR2_3") (pintype "bidirectional"))
    )
    (net (code "51") (name "MAG_DRDY") (class "Default")
      (node (ref "U$501") (pin "12") (pinfunction "DSYNC_12") (pintype "bidirectional"))
      (node (ref "U101") (pin "36") (pinfunction "PB1_36") (pintype "bidirectional"))
    )
    (net (code "52") (name "Net-(C101-1)") (class "Default")
      (node (ref "C101") (pin "P$1") (pinfunction "1_P$1") (pintype "passive"))
      (node (ref "U101") (pin "12") (pinfunction "OSC_IN_12") (pintype "input"))
      (node (ref "X101") (pin "3") (pinfunction "3_3") (pintype "bidirectional"))
    )
    (net (code "53") (name "Net-(C102-2)") (class "Default")
      (node (ref "C102") (pin "P$2") (pinfunction "2_P$2") (pintype "passive"))
      (node (ref "U101") (pin "13") (pinfunction "OSC_OUT_13") (pintype "output"))
      (node (ref "X101") (pin "1") (pinfunction "1_1") (pintype "bidirectional"))
    )
    (net (code "54") (name "Net-(C403-1)") (class "Default")
      (node (ref "C403") (pin "P$1") (pinfunction "1_P$1") (pintype "passive"))
      (node (ref "JP403") (pin "2") (pinfunction "2_2") (pintype "passive"))
      (node (ref "R405") (pin "P$2") (pinfunction "2_P$2") (pintype "passive"))
    )
    (net (code "55") (name "Net-(C404-1)") (class "Default")
      (node (ref "C404") (pin "P$1") (pinfunction "1_P$1") (pintype "passive"))
      (node (ref "JP403") (pin "1") (pinfunction "1_1") (pintype "passive"))
      (node (ref "R406") (pin "P$2") (pinfunction "2_P$2") (pintype "passive"))
    )
    (net (code "56") (name "Net-(C503-1)") (class "Default")
      (node (ref "C503") (pin "P$1") (pinfunction "1_P$1") (pintype "passive"))
      (node (ref "U$501") (pin "13") (pinfunction "REGD_13") (pintype "power_in"))
    )
    (net (code "57") (name "Net-(C603-1)") (class "Default")
      (node (ref "C603") (pin "P$1") (pinfunction "1_P$1") (pintype "passive"))
      (node (ref "U$601") (pin "10") (pinfunction "VAUX_10") (pintype "input"))
    )
    (net (code "58") (name "Net-(C703-2)") (class "Default")
      (node (ref "C703") (pin "P$2") (pinfunction "2_P$2") (pintype "passive"))
      (node (ref "U$701") (pin "6") (pinfunction "CSET_6") (pintype "bidirectional"))
    )
    (net (code "59") (name "Net-(C704-1)") (class "Default")
      (node (ref "C704") (pin "P$1") (pinfunction "1_P$1") (pintype "passive"))
      (node (ref "U$702") (pin "6") (pinfunction "CSET_6") (pintype "bidirectional"))
    )
    (net (code "60") (name "Net-(C715-1)") (class "Default")
      (node (ref "C715") (pin "P$1") (pinfunction "1_P$1") (pintype "passive"))
      (node (ref "U101") (pin "49") (pinfunction "VCAP_1_49") (pintype "power_in"))
    )
    (net (code "61") (name "Net-(C717-1)") (class "Default")
      (node (ref "C717") (pin "P$1") (pinfunction "1_P$1") (pintype "passive"))
      (node (ref "U101") (pin "73") (pinfunction "VCAP_2_73") (pintype "power_in"))
    )
    (net (code "62") (name "Net-(J401-Pad8)") (class "Default")
      (node (ref "J401") (pin "8") (pinfunction "8_8") (pintype "passive"))
      (node (ref "L401") (pin "P$2") (pinfunction "P$2_P$2") (pintype "bidirectional"))
    )
    (net (code "63") (name "Net-(J1001A-S)") (class "Default")
      (node (ref "J1001") (pin "S1") (pinfunction "S_S1") (pintype "passive"))
      (node (ref "L1001") (pin "P$9") (pinfunction "P$2_P$9") (pintype "bidirectional"))
    )
    (net (code "64") (name "Net-(J1001B-S)") (class "Default")
      (node (ref "J1001") (pin "S2") (pinfunction "S_S2") (pintype "passive"))
      (node (ref "L1001") (pin "P$10") (pinfunction "P$2_P$10") (pintype "bidirectional"))
    )
    (net (code "65") (name "Net-(J1001C-S)") (class "Default")
      (node (ref "J1001") (pin "S3") (pinfunction "S_S3") (pintype "passive"))
      (node (ref "L1001") (pin "P$12") (pinfunction "P$2_P$12") (pintype "bidirectional"))
    )
    (net (code "66") (name "Net-(J1001D-S)") (class "Default")
      (node (ref "J1001") (pin "S4") (pinfunction "S_S4") (pintype "passive"))
      (node (ref "L1001") (pin "P$11") (pinfunction "P$2_P$11") (pintype "bidirectional"))
    )
    (net (code "67") (name "Net-(J1001E-S)") (class "Default")
      (node (ref "J1001") (pin "S5") (pinfunction "S_S5") (pintype "passive"))
      (node (ref "L1001") (pin "P$13") (pinfunction "P$2_P$13") (pintype "bidirectional"))
    )
    (net (code "68") (name "Net-(J1001F-S)") (class "Default")
      (node (ref "J1001") (pin "S6") (pinfunction "S_S6") (pintype "passive"))
      (node (ref "L1001") (pin "P$14") (pinfunction "P$2_P$14") (pintype "bidirectional"))
    )
    (net (code "69") (name "Net-(J1001G-S)") (class "Default")
      (node (ref "J1001") (pin "S7") (pinfunction "S_S7") (pintype "passive"))
      (node (ref "L1001") (pin "P$15") (pinfunction "P$2_P$15") (pintype "bidirectional"))
    )
    (net (code "70") (name "Net-(J1001H-S)") (class "Default")
      (node (ref "J1001") (pin "S8") (pinfunction "S_S8") (pintype "passive"))
      (node (ref "L1001") (pin "P$16") (pinfunction "P$2_P$16") (pintype "bidirectional"))
    )
    (net (code "71") (name "Net-(JP201-Pad2)") (class "Default")
      (node (ref "JP201") (pin "2") (pinfunction "2_2") (pintype "passive"))
      (node (ref "JP202") (pin "2") (pinfunction "2_2") (pintype "bidirectional"))
      (node (ref "U$201") (pin "C") (pinfunction "C_C") (pintype "passive"))
    )
    (net (code "72") (name "Net-(JP203-Pad2)") (class "Default")
      (node (ref "JP203") (pin "2") (pinfunction "2_2") (pintype "bidirectional"))
      (node (ref "JP204") (pin "2") (pinfunction "2_2") (pintype "bidirectional"))
      (node (ref "JP205") (pin "2") (pinfunction "2_2") (pintype "bidirectional"))
      (node (ref "L203") (pin "P$2") (pinfunction "P$2_P$2") (pintype "bidirectional"))
      (node (ref "U$204") (pin "C") (pinfunction "C_C") (pintype "passive"))
    )
    (net (code "73") (name "Net-(JP401-Pad1)") (class "Default")
      (node (ref "JP401") (pin "1") (pinfunction "1_1") (pintype "passive"))
      (node (ref "JP402") (pin "1") (pinfunction "1_1") (pintype "passive"))
      (node (ref "L402") (pin "P$2") (pinfunction "P$2_P$2") (pintype "bidirectional"))
      (node (ref "U$401") (pin "C") (pinfunction "C_C") (pintype "passive"))
    )
    (net (code "74") (name "Net-(JP404-Pad1)") (class "Default")
      (node (ref "JP404") (pin "1") (pinfunction "1_1") (pintype "passive"))
      (node (ref "JP405") (pin "1") (pinfunction "1_1") (pintype "passive"))
      (node (ref "L404") (pin "P$2") (pinfunction "P$2_P$2") (pintype "bidirectional"))
      (node (ref "U$402") (pin "C") (pinfunction "C_C") (pintype "passive"))
    )
    (net (code "75") (name "Net-(JP1001-1)") (class "Default")
      (node (ref "JP1001") (pin "P$1") (pinfunction "1_P$1") (pintype "passive"))
      (node (ref "R1001") (pin "P$1") (pinfunction "1_P$1") (pintype "passive"))
    )
    (net (code "76") (name "Net-(JP1002-1)") (class "Default")
      (node (ref "JP1002") (pin "P$1") (pinfunction "1_P$1") (pintype "passive"))
      (node (ref "R1002") (pin "P$1") (pinfunction "1_P$1") (pintype "passive"))
    )
    (net (code "77") (name "Net-(L403B-P$2)") (class "Default")
      (node (ref "JP402") (pin "2") (pinfunction "2_2") (pintype "passive"))
      (node (ref "L403") (pin "P$15") (pinfunction "P$2_P$15") (pintype "bidirectional"))
    )
    (net (code "78") (name "Net-(L403D-P$2)") (class "Default")
      (node (ref "JP401") (pin "2") (pinfunction "2_2") (pintype "passive"))
      (node (ref "L403") (pin "P$13") (pinfunction "P$2_P$13") (pintype "bidirectional"))
    )
    (net (code "79") (name "Net-(L403G-P$2)") (class "Default")
      (node (ref "JP402") (pin "3") (pinfunction "3_3") (pintype "passive"))
      (node (ref "L403") (pin "P$10") (pinfunction "P$2_P$10") (pintype "bidirectional"))
    )
    (net (code "80") (name "Net-(L403H-P$2)") (class "Default")
      (node (ref "JP401") (pin "3") (pinfunction "3_3") (pintype "passive"))
      (node (ref "L403") (pin "P$9") (pinfunction "P$2_P$9") (pintype "bidirectional"))
    )
    (net (code "81") (name "Net-(R101-1)") (class "Default")
      (node (ref "R101") (pin "P$1") (pinfunction "1_P$1") (pintype "passive"))
      (node (ref "U101") (pin "37") (pinfunction "PB2_37") (pintype "bidirectional"))
    )
    (net (code "82") (name "Net-(R201-2)") (class "Default")
      (node (ref "JP202") (pin "1") (pinfunction "1_1") (pintype "bidirectional"))
      (node (ref "R201") (pin "P$2") (pinfunction "2_P$2") (pintype "passive"))
      (node (ref "R202") (pin "P$2") (pinfunction "2_P$2") (pintype "passive"))
      (node (ref "U$202") (pin "C") (pinfunction "C_C") (pintype "passive"))
    )
    (net (code "83") (name "Net-(R407-2)") (class "Default")
      (node (ref "R407") (pin "P$2") (pinfunction "2_P$2") (pintype "passive"))
      (node (ref "SJ402") (pin "1") (pinfunction "1_1") (pintype "passive"))
    )
    (net (code "84") (name "Net-(R408-1)") (class "Default")
      (node (ref "R408") (pin "P$1") (pinfunction "1_P$1") (pintype "passive"))
      (node (ref "SJ401") (pin "2") (pinfunction "2_2") (pintype "passive"))
    )
    (net (code "85") (name "Net-(R408-2)") (class "Default")
      (node (ref "JP404") (pin "3") (pinfunction "3_3") (pintype "passive"))
      (node (ref "R408") (pin "P$2") (pinfunction "2_P$2") (pintype "passive"))
      (node (ref "U401") (pin "6") (pinfunction "CANL_6") (pintype "bidirectional"))
    )
    (net (code "86") (name "Net-(R703-1)") (class "Default")
      (node (ref "R703") (pin "P$1") (pinfunction "1_P$1") (pintype "passive"))
      (node (ref "U$703") (pin "7") (pinfunction "ILIM_7") (pintype "bidirectional"))
    )
    (net (code "87") (name "Net-(R706-2)") (class "Default")
      (node (ref "D701") (pin "C") (pinfunction "C_C") (pintype "passive"))
      (node (ref "R706") (pin "P$2") (pinfunction "2_P$2") (pintype "passive"))
    )
    (net (code "88") (name "Net-(R801-1)") (class "Default")
      (node (ref "JP801") (pin "2") (pinfunction "2_2") (pintype "passive"))
      (node (ref "R801") (pin "P$1") (pinfunction "1_P$1") (pintype "passive"))
    )
    (net (code "89") (name "Net-(R803-1)") (class "Default")
      (node (ref "R803") (pin "P$1") (pinfunction "1_P$1") (pintype "passive"))
      (node (ref "R804") (pin "P$2") (pinfunction "2_P$2") (pintype "passive"))
    )
    (net (code "90") (name "Net-(R803-2)") (class "Default")
      (node (ref "LED801") (pin "C") (pinfunction "C_C") (pintype "passive"))
      (node (ref "R803") (pin "P$2") (pinfunction "2_P$2") (pintype "passive"))
    )
    (net (code "91") (name "Net-(R805-2)") (class "Default")
      (node (ref "LED802") (pin "C") (pinfunction "C_C") (pintype "passive"))
      (node (ref "R805") (pin "P$2") (pinfunction "2_P$2") (pintype "passive"))
    )
    (net (code "92") (name "Net-(R901-1)") (class "Default")
      (node (ref "D901") (pin "C") (pinfunction "C_C") (pintype "passive"))
      (node (ref "R901") (pin "P$1") (pinfunction "1_P$1") (pintype "passive"))
      (node (ref "R902") (pin "P$2") (pinfunction "2_P$2") (pintype "passive"))
    )
    (net (code "93") (name "Net-(U$301-D1I)") (class "Default")
      (node (ref "JP301") (pin "2") (pinfunction "2_2") (pintype "passive"))
      (node (ref "U$301") (pin "1") (pinfunction "D1I_1") (pintype "bidirectional"))
    )
    (net (code "94") (name "Net-(U$301-D2I)") (class "Default")
      (node (ref "JP301") (pin "3") (pinfunction "3_3") (pintype "passive"))
      (node (ref "U$301") (pin "3") (pinfunction "D2I_3") (pintype "bidirectional"))
    )
    (net (code "95") (name "Net-(U$601-L1)") (class "Default")
      (node (ref "L$601") (pin "2") (pinfunction "2_2") (pintype "passive"))
      (node (ref "U$601") (pin "1") (pinfunction "L1_1") (pintype "bidirectional"))
    )
    (net (code "96") (name "Net-(U$601-L2)") (class "Default")
      (node (ref "L$601") (pin "1") (pinfunction "1_1") (pintype "passive"))
      (node (ref "U$601") (pin "14") (pinfunction "L2_14") (pintype "bidirectional"))
    )
    (net (code "97") (name "Net-(U401-CANH)") (class "Default")
      (node (ref "JP404") (pin "2") (pinfunction "2_2") (pintype "passive"))
      (node (ref "SJ401") (pin "1") (pinfunction "1_1") (pintype "passive"))
      (node (ref "U401") (pin "7") (pinfunction "CANH_7") (pintype "bidirectional"))
    )
    (net (code "98") (name "OTG_FS_DM") (class "Default")
      (node (ref "U$301") (pin "6") (pinfunction "D1O_6") (pintype "bidirectional"))
      (node (ref "U101") (pin "70") (pinfunction "PA11_70") (pintype "bidirectional"))
    )
    (net (code "99") (name "OTG_FS_DP") (class "Default")
      (node (ref "U$301") (pin "4") (pinfunction "D2O_4") (pintype "bidirectional"))
      (node (ref "U101") (pin "71") (pinfunction "PA12_71") (pintype "bidirectional"))
    )
    (net (code "100") (name "PPM_INPUT") (class "Default")
      (node (ref "R201") (pin "P$1") (pinfunction "1_P$1") (pintype "passive"))
      (node (ref "R203") (pin "P$1") (pinfunction "1_P$1") (pintype "passive"))
      (node (ref "U$203") (pin "2") (pinfunction "1A_2") (pintype "bidirectional"))
      (node (ref "U101") (pin "23") (pinfunction "PA0_23") (pintype "bidirectional"))
    )
    (net (code "101") (name "SAFETY") (class "Default")
      (node (ref "JP801") (pin "3") (pinfunction "3_3") (pintype "passive"))
      (node (ref "R802") (pin "P$1") (pinfunction "1_P$1") (pintype "passive"))
      (node (ref "U101") (pin "93") (pinfunction "PB7_93") (pintype "bidirectional"))
    )
    (net (code "102") (name "SBUS_OUTPUT_ENABLE") (class "Default")
      (node (ref "R204") (pin "P$2") (pinfunction "2_P$2") (pintype "passive"))
      (node (ref "U$203") (pin "7") (pinfunction "~{2OE}_7") (pintype "input"))
      (node (ref "U101") (pin "91") (pinfunction "PB5_91") (pintype "bidirectional"))
    )
    (net (code "103") (name "SDIO_CK") (class "Default")
      (node (ref "U101") (pin "80") (pinfunction "PC12_80") (pintype "bidirectional"))
    )
    (net (code "104") (name "SDIO_CMD") (class "Default")
      (node (ref "U101") (pin "83") (pinfunction "PD2_83") (pintype "bidirectional"))
    )
    (net (code "105") (name "SDIO_D0") (class "Default")
      (node (ref "U101") (pin "65") (pinfunction "PC8_65") (pintype "bidirectional"))
    )
    (net (code "106") (name "SDIO_D1") (class "Default")
      (node (ref "U101") (pin "66") (pinfunction "PC9_66") (pintype "bidirectional"))
    )
    (net (code "107") (name "SDIO_D2") (class "Default")
      (node (ref "U101") (pin "78") (pinfunction "PC10_78") (pintype "bidirectional"))
    )
    (net (code "108") (name "SDIO_D3") (class "Default")
      (node (ref "U101") (pin "79") (pinfunction "PC11_79") (pintype "bidirectional"))
    )
    (net (code "109") (name "SERIAL1_CTS") (class "Default")
      (node (ref "JP203") (pin "6") (pinfunction "6_6") (pintype "bidirectional"))
      (node (ref "L201") (pin "P$16") (pinfunction "P$2_P$16") (pintype "bidirectional"))
    )
    (net (code "110") (name "SERIAL1_RTS") (class "Default")
      (node (ref "JP203") (pin "4") (pinfunction "4_4") (pintype "bidirectional"))
      (node (ref "L201") (pin "P$15") (pinfunction "P$2_P$15") (pintype "bidirectional"))
    )
    (net (code "111") (name "SERIAL1_RX") (class "Default")
      (node (ref "JP203") (pin "3") (pinfunction "3_3") (pintype "bidirectional"))
      (node (ref "L201") (pin "P$13") (pinfunction "P$2_P$13") (pintype "bidirectional"))
    )
    (net (code "112") (name "SERIAL1_TX") (class "Default")
      (node (ref "JP203") (pin "1") (pinfunction "1_1") (pintype "bidirectional"))
      (node (ref "L201") (pin "P$14") (pinfunction "P$2_P$14") (pintype "bidirectional"))
    )
    (net (code "113") (name "SERIAL2_CTS") (class "Default")
      (node (ref "JP204") (pin "6") (pinfunction "6_6") (pintype "bidirectional"))
      (node (ref "L201") (pin "P$10") (pinfunction "P$2_P$10") (pintype "bidirectional"))
    )
    (net (code "114") (name "SERIAL2_RTS") (class "Default")
      (node (ref "JP204") (pin "4") (pinfunction "4_4") (pintype "bidirectional"))
      (node (ref "L201") (pin "P$9") (pinfunction "P$2_P$9") (pintype "bidirectional"))
    )
    (net (code "115") (name "SERIAL2_RX") (class "Default")
      (node (ref "JP204") (pin "3") (pinfunction "3_3") (pintype "bidirectional"))
      (node (ref "L201") (pin "P$11") (pinfunction "P$2_P$11") (pintype "bidirectional"))
    )
    (net (code "116") (name "SERIAL2_TX") (class "Default")
      (node (ref "JP204") (pin "1") (pinfunction "1_1") (pintype "bidirectional"))
      (node (ref "L201") (pin "P$12") (pinfunction "P$2_P$12") (pintype "bidirectional"))
    )
    (net (code "117") (name "SERIAL3_RX") (class "Default")
      (node (ref "JP205") (pin "3") (pinfunction "3_3") (pintype "bidirectional"))
      (node (ref "L202") (pin "P$9") (pinfunction "P$2_P$9") (pintype "bidirectional"))
    )
    (net (code "118") (name "SERIAL3_TX") (class "Default")
      (node (ref "JP205") (pin "1") (pinfunction "1_1") (pintype "bidirectional"))
      (node (ref "L202") (pin "P$11") (pinfunction "P$2_P$11") (pintype "bidirectional"))
    )
    (net (code "119") (name "SPEKTRUM_RX") (class "Default")
      (node (ref "R202") (pin "P$1") (pinfunction "1_P$1") (pintype "passive"))
      (node (ref "U101") (pin "69") (pinfunction "PA10_69") (pintype "bidirectional"))
    )
    (net (code "120") (name "SPI_EXT_MISO") (class "Default")
      (node (ref "J401") (pin "3") (pinfunction "3_3") (pintype "passive"))
      (node (ref "U101") (pin "4") (pinfunction "PE5_4") (pintype "bidirectional"))
    )
    (net (code "121") (name "SPI_EXT_MOSI") (class "Default")
      (node (ref "J401") (pin "6") (pinfunction "6_6") (pintype "passive"))
      (node (ref "U101") (pin "5") (pinfunction "PE6_5") (pintype "bidirectional"))
    )
    (net (code "122") (name "SPI_EXT_SCK") (class "Default")
      (node (ref "J401") (pin "2") (pinfunction "2_2") (pintype "passive"))
      (node (ref "U101") (pin "1") (pinfunction "PE2_1") (pintype "bidirectional"))
    )
    (net (code "123") (name "SPI_INT_MISO") (class "Default")
      (node (ref "U$501") (pin "7") (pinfunction "SA0/MISO_7") (pintype "bidirectional"))
      (node (ref "U101") (pin "31") (pinfunction "PA6_31") (pintype "bidirectional"))
    )
    (net (code "124") (name "SPI_INT_MOSI") (class "Default")
      (node (ref "U$501") (pin "6") (pinfunction "SDA/MOSI_6") (pintype "bidirectional"))
      (node (ref "U101") (pin "32") (pinfunction "PA7_32") (pintype "bidirectional"))
    )
    (net (code "125") (name "SPI_INT_SCK") (class "Default")
      (node (ref "U$501") (pin "4") (pinfunction "SCL/CLK_4") (pintype "bidirectional"))
      (node (ref "U101") (pin "30") (pinfunction "PA5_30") (pintype "bidirectional"))
    )
    (net (code "126") (name "VBAT") (class "Default")
      (node (ref "R706") (pin "P$1") (pinfunction "1_P$1") (pintype "passive"))
      (node (ref "U$704") (pin "1") (pinfunction "POS_1") (pintype "bidirectional"))
      (node (ref "U101") (pin "6") (pinfunction "VBAT_6") (pintype "power_in"))
    )
    (net (code "127") (name "VBUS") (class "Default")
      (node (ref "D904") (pin "ANODE") (pinfunction "A_ANODE") (pintype "passive"))
      (node (ref "JP301") (pin "1") (pinfunction "1_1") (pintype "passive"))
      (node (ref "U$301") (pin "5") (pinfunction "VBUS_5") (pintype "bidirectional"))
      (node (ref "U101") (pin "68") (pinfunction "PA9_68") (pintype "bidirectional"))
    )
    (net (code "128") (name "VDD_3V3_SENSORS") (class "Default")
      (node (ref "C501") (pin "P$1") (pinfunction "1_P$1") (pintype "passive"))
      (node (ref "C502") (pin "P$1") (pinfunction "1_P$1") (pintype "passive"))
      (node (ref "C707") (pin "P$1") (pinfunction "1_P$1") (pintype "passive"))
      (node (ref "U$501") (pin "1") (pinfunction "VDD_IO_1") (pintype "power_in"))
      (node (ref "U$501") (pin "14") (pinfunction "VDD_14") (pintype "power_in"))
      (node (ref "U$501") (pin "15") (pinfunction "RSV2_15") (pintype "input"))
      (node (ref "U$702") (pin "8") (pinfunction "VOUT1_8") (pintype "bidirectional"))
    )
    (net (code "129") (name "VDD_3V3_SENSORS_EN") (class "Default")
      (node (ref "R702") (pin "P$2") (pinfunction "2_P$2") (pintype "passive"))
      (node (ref "U$702") (pin "5") (pinfunction "EN1_5") (pintype "bidirectional"))
      (node (ref "U101") (pin "2") (pinfunction "PE3_2") (pintype "bidirectional"))
    )
    (net (code "130") (name "VDD_3V3_SPEKTRUM") (class "Default")
      (node (ref "C708") (pin "P$1") (pinfunction "1_P$1") (pintype "passive"))
      (node (ref "JP201") (pin "1") (pinfunction "1_1") (pintype "passive"))
      (node (ref "U$701") (pin "8") (pinfunction "VOUT1_8") (pintype "bidirectional"))
    )
    (net (code "131") (name "VDD_3V3_SPEKTRUM_EN") (class "Default")
      (node (ref "R701") (pin "P$2") (pinfunction "2_P$2") (pintype "passive"))
      (node (ref "U$701") (pin "5") (pinfunction "EN1_5") (pintype "bidirectional"))
      (node (ref "U101") (pin "17") (pinfunction "PC2_17") (pintype "bidirectional"))
    )
    (net (code "132") (name "VDD_5V") (class "Default")
      (node (ref "C604") (pin "1") (pinfunction "1_1") (pintype "passive"))
      (node (ref "C605") (pin "1") (pinfunction "1_1") (pintype "passive"))
      (node (ref "C606") (pin "1") (pinfunction "1_1") (pintype "passive"))
      (node (ref "C701") (pin "P$1") (pinfunction "1_P$1") (pintype "passive"))
      (node (ref "C702") (pin "P$1") (pinfunction "1_P$1") (pintype "passive"))
      (node (ref "LED801") (pin "A") (pinfunction "A_A") (pintype "passive"))
      (node (ref "LED802") (pin "A") (pinfunction "A_A") (pintype "passive"))
      (node (ref "R707") (pin "P$2") (pinfunction "2_P$2") (pintype "passive"))
      (node (ref "U$601") (pin "13") (pinfunction "VOUT_13") (pintype "power_in"))
      (node (ref "U$701") (pin "1") (pinfunction "VIN_1") (pintype "bidirectional"))
      (node (ref "U$701") (pin "4") (pinfunction "EN2_4") (pintype "bidirectional"))
      (node (ref "U$702") (pin "1") (pinfunction "VIN_1") (pintype "bidirectional"))
      (node (ref "U$703") (pin "1") (pinfunction "IN_1") (pintype "bidirectional"))
    )
    (net (code "133") (name "VDD_5V_PERIPH") (class "Default")
      (node (ref "JP201") (pin "3") (pinfunction "3_3") (pintype "passive"))
      (node (ref "L203") (pin "P$1") (pinfunction "P$1_P$1") (pintype "bidirectional"))
      (node (ref "L401") (pin "P$1") (pinfunction "P$1_P$1") (pintype "bidirectional"))
      (node (ref "L402") (pin "P$1") (pinfunction "P$1_P$1") (pintype "bidirectional"))
      (node (ref "L404") (pin "P$1") (pinfunction "P$1_P$1") (pintype "bidirectional"))
      (node (ref "U$703") (pin "8") (pinfunction "OUT_8") (pintype "bidirectional"))
    )
    (net (code "134") (name "VDD_5V_SENS") (class "Default")
      (node (ref "R707") (pin "P$1") (pinfunction "1_P$1") (pintype "passive"))
      (node (ref "R708") (pin "P$1") (pinfunction "1_P$1") (pintype "passive"))
      (node (ref "U101") (pin "29") (pinfunction "PA4_29") (pintype "bidirectional"))
    )
    (net (code "135") (name "VDD_IN") (class "Default")
      (node (ref "C601") (pin "1") (pinfunction "1_1") (pintype "passive"))
      (node (ref "C602") (pin "P$1") (pinfunction "1_P$1") (pintype "passive"))
      (node (ref "D902") (pin "C") (pinfunction "C_C") (pintype "passive"))
      (node (ref "D903") (pin "C") (pinfunction "C_C") (pintype "passive"))
      (node (ref "D904") (pin "CATHODE") (pinfunction "C_CATHODE") (pintype "passive"))
      (node (ref "U$601") (pin "2") (pinfunction "VIN_2") (pintype "power_in"))
      (node (ref "U$601") (pin "3") (pinfunction "EN_3") (pintype "input"))
    )
    (net (code "136") (name "VDD_SERVO_SENSE") (class "Default")
      (node (ref "R902") (pin "P$1") (pinfunction "1_P$1") (pintype "passive"))
      (node (ref "R903") (pin "P$2") (pinfunction "2_P$2") (pintype "passive"))
      (node (ref "U101") (pin "16") (pinfunction "PC1_16") (pintype "bidirectional"))
    )
    (net (code "137") (name "V_EXT") (class "Default")
      (node (ref "D903") (pin "A") (pinfunction "A_A") (pintype "passive"))
      (node (ref "JP901") (pin "1") (pinfunction "1_1") (pintype "passive"))
      (node (ref "R901") (pin "P$2") (pinfunction "2_P$2") (pintype "passive"))
    )
    (net (code "138") (name "V_SERVO") (class "Default")
      (node (ref "D902") (pin "A") (pinfunction "A_A") (pintype "passive"))
      (node (ref "J1001") (pin "PWR_S1") (pinfunction "S_PWR_S1") (pintype "passive"))
      (node (ref "J1001") (pin "PWR_S2") (pinfunction "S_PWR_S2") (pintype "passive"))
      (node (ref "J1001") (pin "PWR_S3") (pinfunction "S_PWR_S3") (pintype "passive"))
      (node (ref "J1001") (pin "PWR_S4") (pinfunction "S_PWR_S4") (pintype "passive"))
      (node (ref "J1001") (pin "PWR_S5") (pinfunction "S_PWR_S5") (pintype "passive"))
      (node (ref "J1001") (pin "PWR_S6") (pinfunction "S_PWR_S6") (pintype "passive"))
      (node (ref "J1001") (pin "PWR_S7") (pinfunction "S_PWR_S7") (pintype "passive"))
      (node (ref "J1001") (pin "PWR_S8") (pinfunction "S_PWR_S8") (pintype "passive"))
    )
    (net (code "139") (name "unconnected-(J401-Pad1)") (class "Default")
      (node (ref "J401") (pin "1") (pinfunction "1_1") (pintype "passive"))
    )
    (net (code "140") (name "unconnected-(JP205-Pad4)") (class "Default")
      (node (ref "JP205") (pin "4") (pinfunction "4_4") (pintype "bidirectional"))
    )
    (net (code "141") (name "unconnected-(JP205-Pad6)") (class "Default")
      (node (ref "JP205") (pin "6") (pinfunction "6_6") (pintype "bidirectional"))
    )
    (net (code "142") (name "unconnected-(JX301F-S-Pad8)") (class "Default")
      (node (ref "JX301") (pin "8") (pinfunction "S_8") (pintype "passive"))
    )
    (net (code "143") (name "unconnected-(L202-PadP$1)") (class "Default")
      (node (ref "L202") (pin "P$1") (pinfunction "P$1_P$1") (pintype "bidirectional"))
    )
    (net (code "144") (name "unconnected-(L202A-P$2-PadP$16)") (class "Default")
      (node (ref "L202") (pin "P$16") (pinfunction "P$2_P$16") (pintype "bidirectional"))
    )
    (net (code "145") (name "unconnected-(L202B-P$1-PadP$2)") (class "Default")
      (node (ref "L202") (pin "P$2") (pinfunction "P$1_P$2") (pintype "bidirectional"))
    )
    (net (code "146") (name "unconnected-(L202B-P$2-PadP$15)") (class "Default")
      (node (ref "L202") (pin "P$15") (pinfunction "P$2_P$15") (pintype "bidirectional"))
    )
    (net (code "147") (name "unconnected-(L202C-P$1-PadP$3)") (class "Default")
      (node (ref "L202") (pin "P$3") (pinfunction "P$1_P$3") (pintype "bidirectional"))
    )
    (net (code "148") (name "unconnected-(L202C-P$2-PadP$14)") (class "Default")
      (node (ref "L202") (pin "P$14") (pinfunction "P$2_P$14") (pintype "bidirectional"))
    )
    (net (code "149") (name "unconnected-(L202D-P$1-PadP$4)") (class "Default")
      (node (ref "L202") (pin "P$4") (pinfunction "P$1_P$4") (pintype "bidirectional"))
    )
    (net (code "150") (name "unconnected-(L202D-P$2-PadP$13)") (class "Default")
      (node (ref "L202") (pin "P$13") (pinfunction "P$2_P$13") (pintype "bidirectional"))
    )
    (net (code "151") (name "unconnected-(L202E-P$1-PadP$5)") (class "Default")
      (node (ref "L202") (pin "P$5") (pinfunction "P$1_P$5") (pintype "bidirectional"))
    )
    (net (code "152") (name "unconnected-(L202E-P$2-PadP$12)") (class "Default")
      (node (ref "L202") (pin "P$12") (pinfunction "P$2_P$12") (pintype "bidirectional"))
    )
    (net (code "153") (name "unconnected-(L202G-P$1-PadP$7)") (class "Default")
      (node (ref "L202") (pin "P$7") (pinfunction "P$1_P$7") (pintype "bidirectional"))
    )
    (net (code "154") (name "unconnected-(L202G-P$2-PadP$10)") (class "Default")
      (node (ref "L202") (pin "P$10") (pinfunction "P$2_P$10") (pintype "bidirectional"))
    )
    (net (code "155") (name "unconnected-(U$501-MST_SCL-Pad2)") (class "Default")
      (node (ref "U$501") (pin "2") (pinfunction "MST_SCL_2") (pintype "bidirectional"))
    )
    (net (code "156") (name "unconnected-(U$501-MST_SDA-Pad3)") (class "Default")
      (node (ref "U$501") (pin "3") (pinfunction "MST_SDA_3") (pintype "bidirectional"))
    )
    (net (code "157") (name "unconnected-(U$501-RSV3-Pad16)") (class "Default")
      (node (ref "U$501") (pin "16") (pinfunction "RSV3_16") (pintype "no_connect"))
    )
    (net (code "158") (name "unconnected-(U$601-FB-Pad12)") (class "Default")
      (node (ref "U$601") (pin "12") (pinfunction "FB_12") (pintype "input"))
    )
    (net (code "159") (name "unconnected-(U$601-PG-Pad5)") (class "Default")
      (node (ref "U$601") (pin "5") (pinfunction "PG_5") (pintype "output"))
    )
    (net (code "160") (name "unconnected-(U$702-VOUT2-Pad7)") (class "Default")
      (node (ref "U$702") (pin "7") (pinfunction "VOUT2_7") (pintype "bidirectional"))
    )
    (net (code "161") (name "unconnected-(U101I-PC0-Pad15)") (class "Default")
      (node (ref "U101") (pin "15") (pinfunction "PC0_15") (pintype "bidirectional"))
    )
    (net (code "162") (name "unconnected-(U101I-PC5-Pad34)") (class "Default")
      (node (ref "U101") (pin "34") (pinfunction "PC5_34") (pintype "bidirectional"))
    )
    (net (code "163") (name "unconnected-(U101I-PC6-Pad63)") (class "Default")
      (node (ref "U101") (pin "63") (pinfunction "PC6_63") (pintype "bidirectional"))
    )
    (net (code "164") (name "unconnected-(U101I-PC7-Pad64)") (class "Default")
      (node (ref "U101") (pin "64") (pinfunction "PC7_64") (pintype "bidirectional"))
    )
    (net (code "165") (name "unconnected-(U101L-PE10-Pad41)") (class "Default")
      (node (ref "U101") (pin "41") (pinfunction "PE10_41") (pintype "bidirectional"))
    )
    (net (code "166") (name "~{BARO_CS}") (class "Default")
      (node (ref "U101") (pin "88") (pinfunction "PD7_88") (pintype "bidirectional"))
    )
    (net (code "167") (name "~{FMU-LED_AMBER}") (class "Default")
      (node (ref "R804") (pin "P$1") (pinfunction "1_P$1") (pintype "passive"))
      (node (ref "U101") (pin "43") (pinfunction "PE12_43") (pintype "bidirectional"))
    )
    (net (code "168") (name "~{FRAM_CS}") (class "Default")
      (node (ref "U$302") (pin "1") (pinfunction "~{CS}_1") (pintype "bidirectional"))
      (node (ref "U101") (pin "57") (pinfunction "PD10_57") (pintype "bidirectional"))
    )
    (net (code "169") (name "~{GYRO_CS}") (class "Default")
      (node (ref "U$501") (pin "8") (pinfunction "CS_8") (pintype "bidirectional"))
      (node (ref "U101") (pin "7") (pinfunction "PC13_7") (pintype "bidirectional"))
    )
    (net (code "170") (name "~{SPI_EXT_NSS}") (class "Default")
      (node (ref "J401") (pin "4") (pinfunction "4_4") (pintype "passive"))
      (node (ref "U101") (pin "3") (pinfunction "PE4_3") (pintype "bidirectional"))
    )
    (net (code "171") (name "~{VDD_5V_PERIPH_EN}") (class "Default")
      (node (ref "R704") (pin "P$2") (pinfunction "2_P$2") (pintype "passive"))
      (node (ref "U$703") (pin "5") (pinfunction "~{CE}_5") (pintype "bidirectional"))
      (node (ref "U101") (pin "67") (pinfunction "PA8_67") (pintype "bidirectional"))
    )
    (net (code "172") (name "~{VDD_5V_PERIPH_OC}") (class "Default")
      (node (ref "R705") (pin "P$2") (pinfunction "2_P$2") (pintype "passive"))
      (node (ref "U$703") (pin "4") (pinfunction "~{FAULT}_4") (pintype "bidirectional"))
      (node (ref "U101") (pin "46") (pinfunction "PE15_46") (pintype "bidirectional"))
    )
  )
)
